# Master.net
KiCad netlist of a schematic drawn in EAGLE
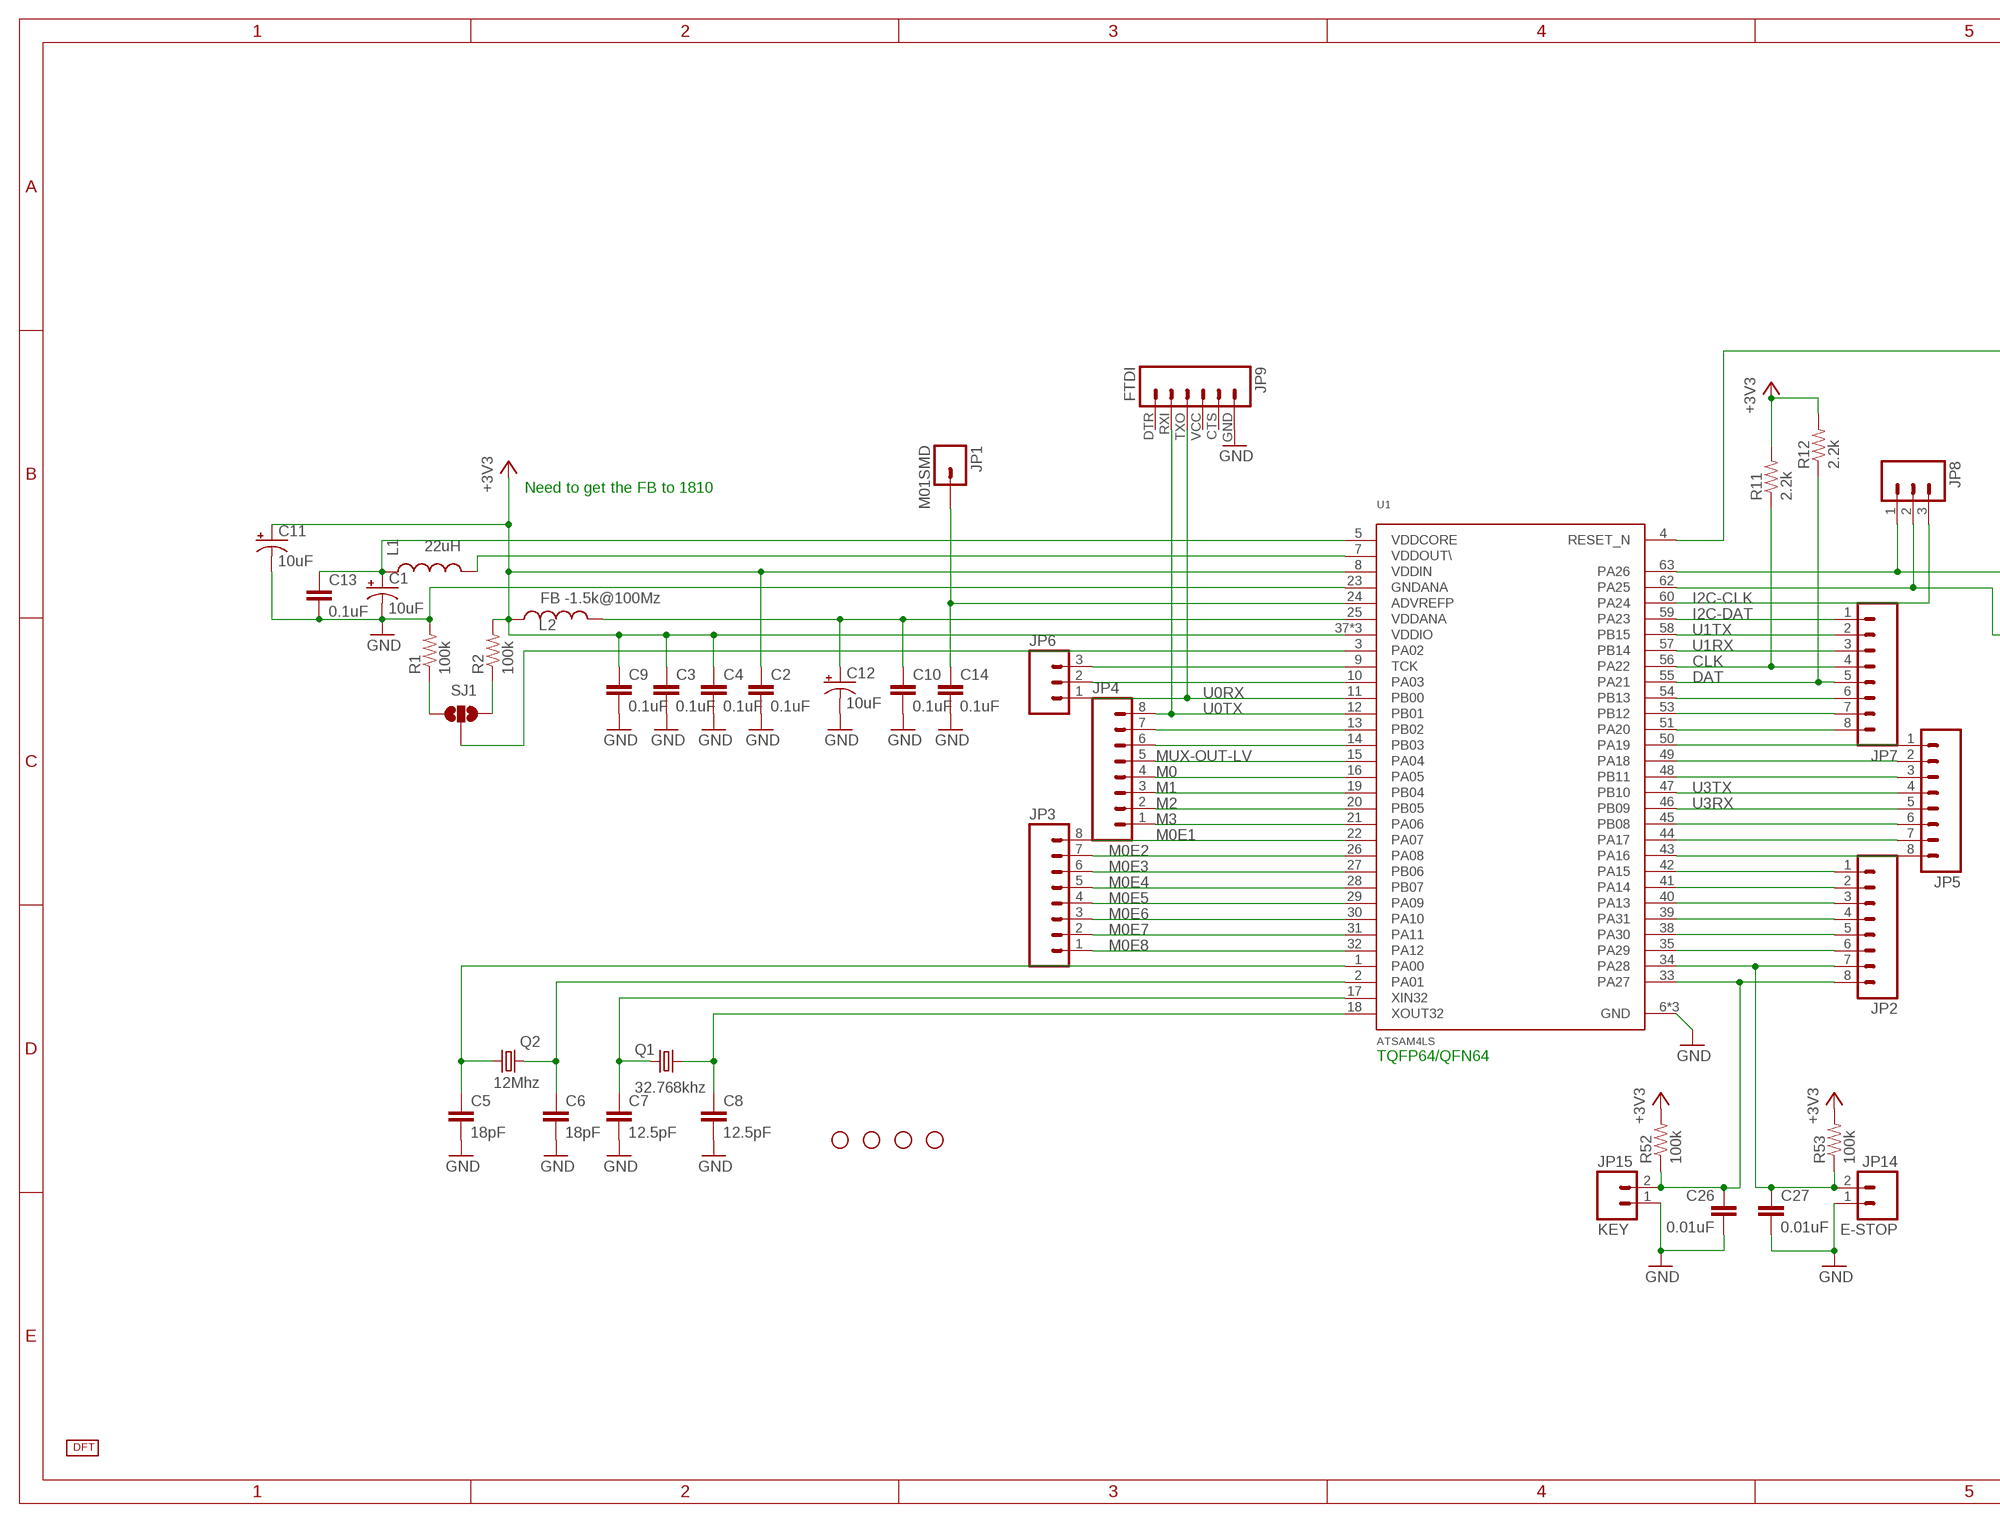
[diagram p0: schematic, sheet 1, part 1 of 2]
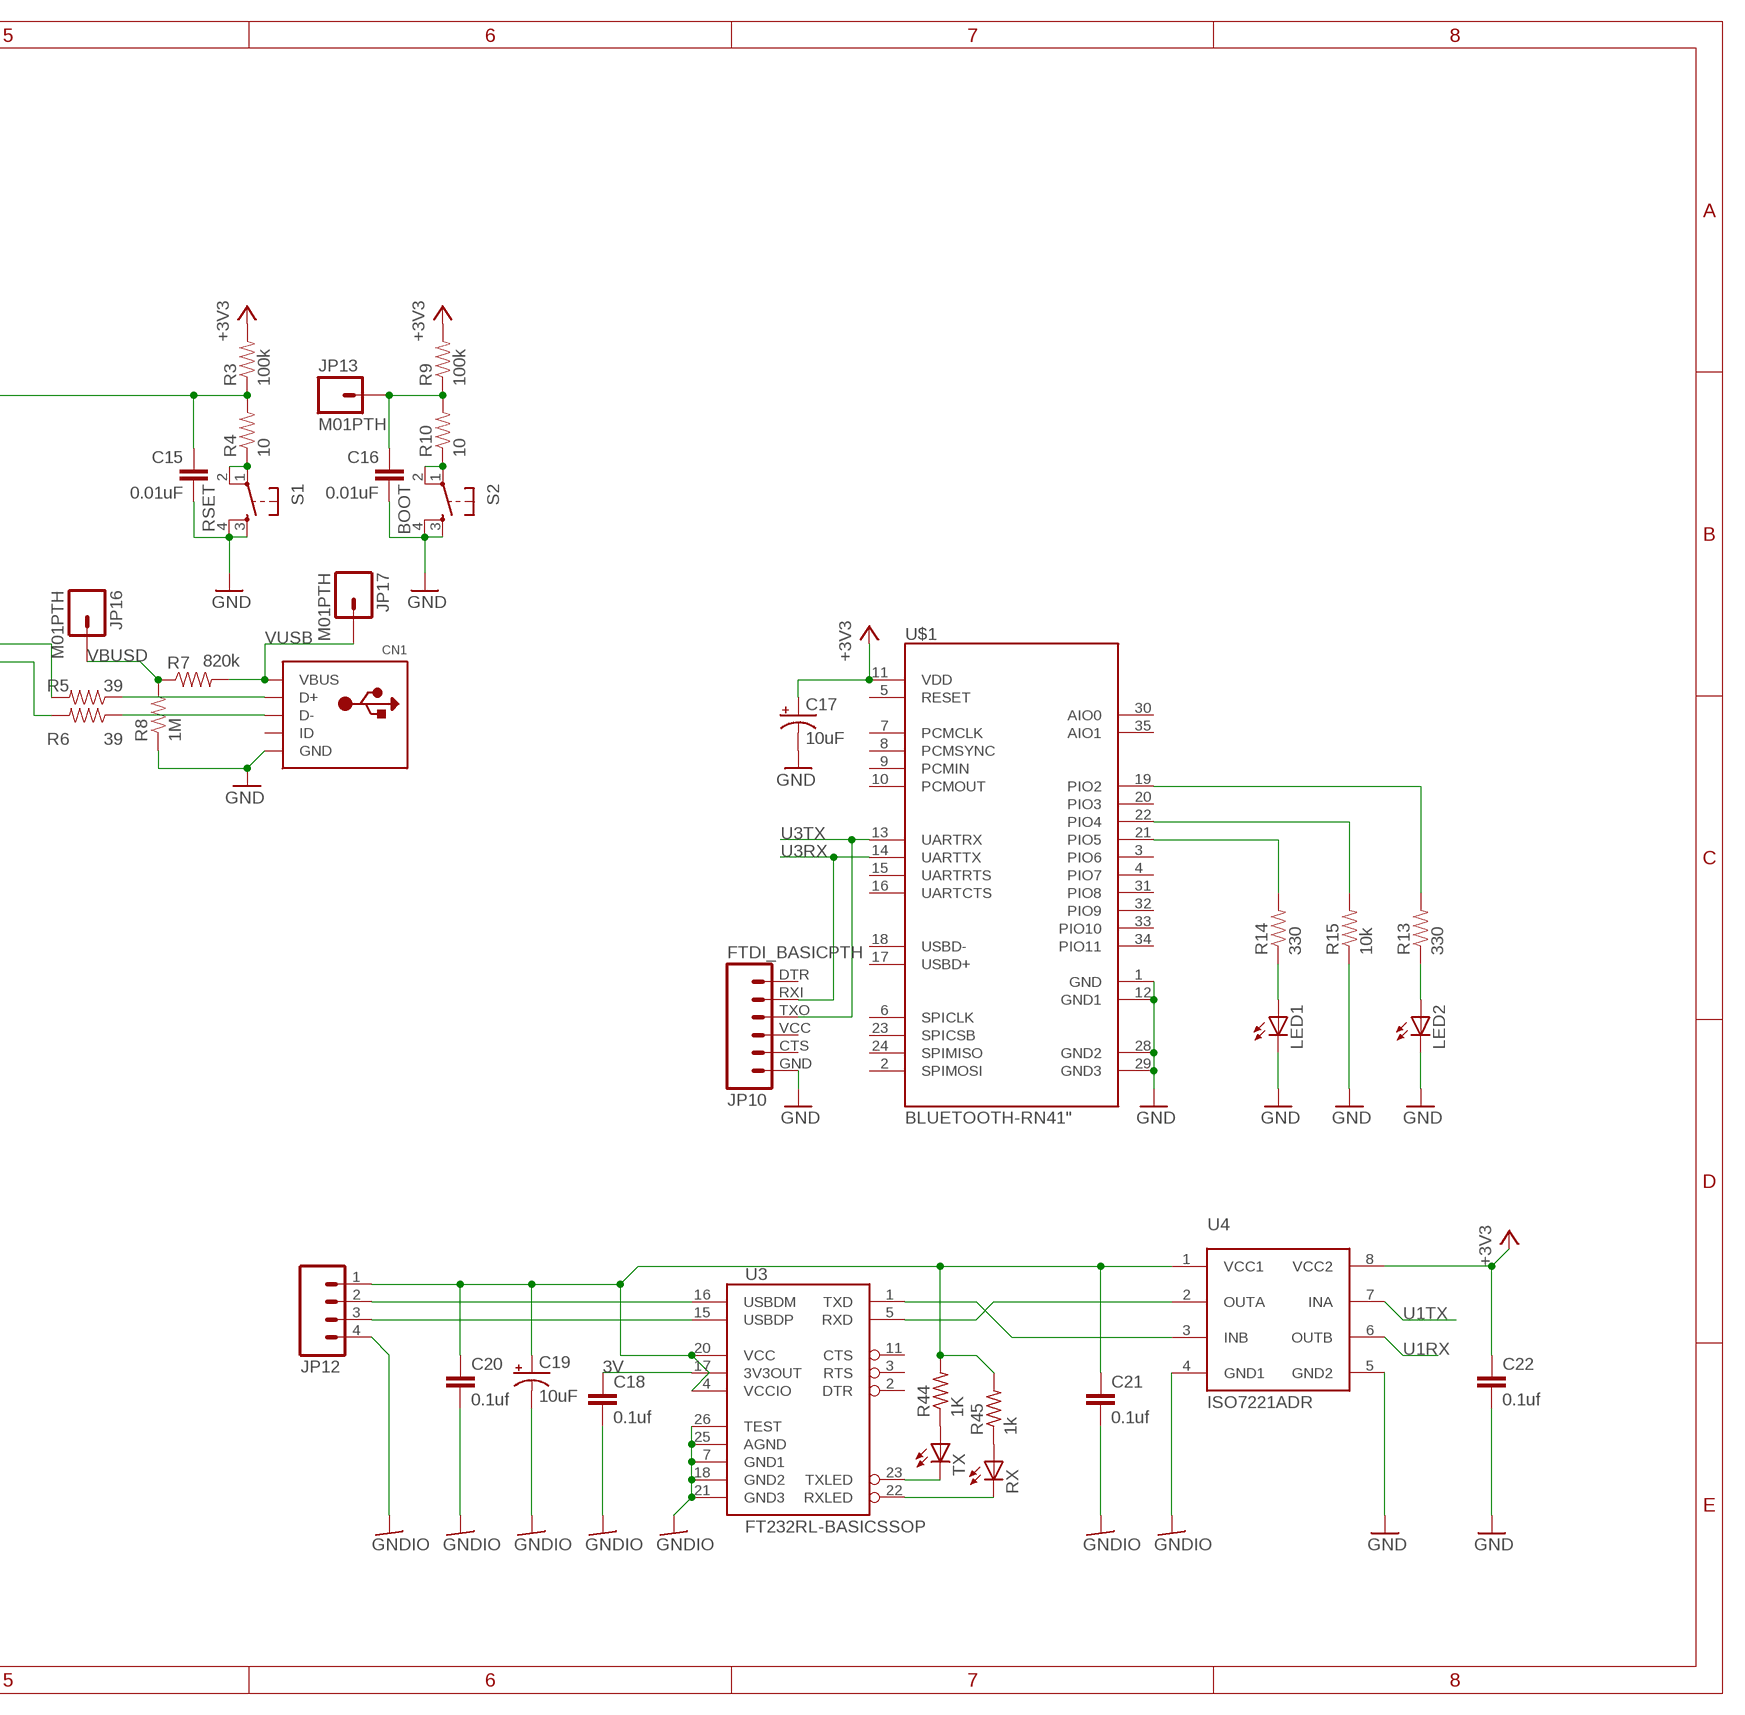
[diagram p1: schematic, sheet 1, part 2 of 2]
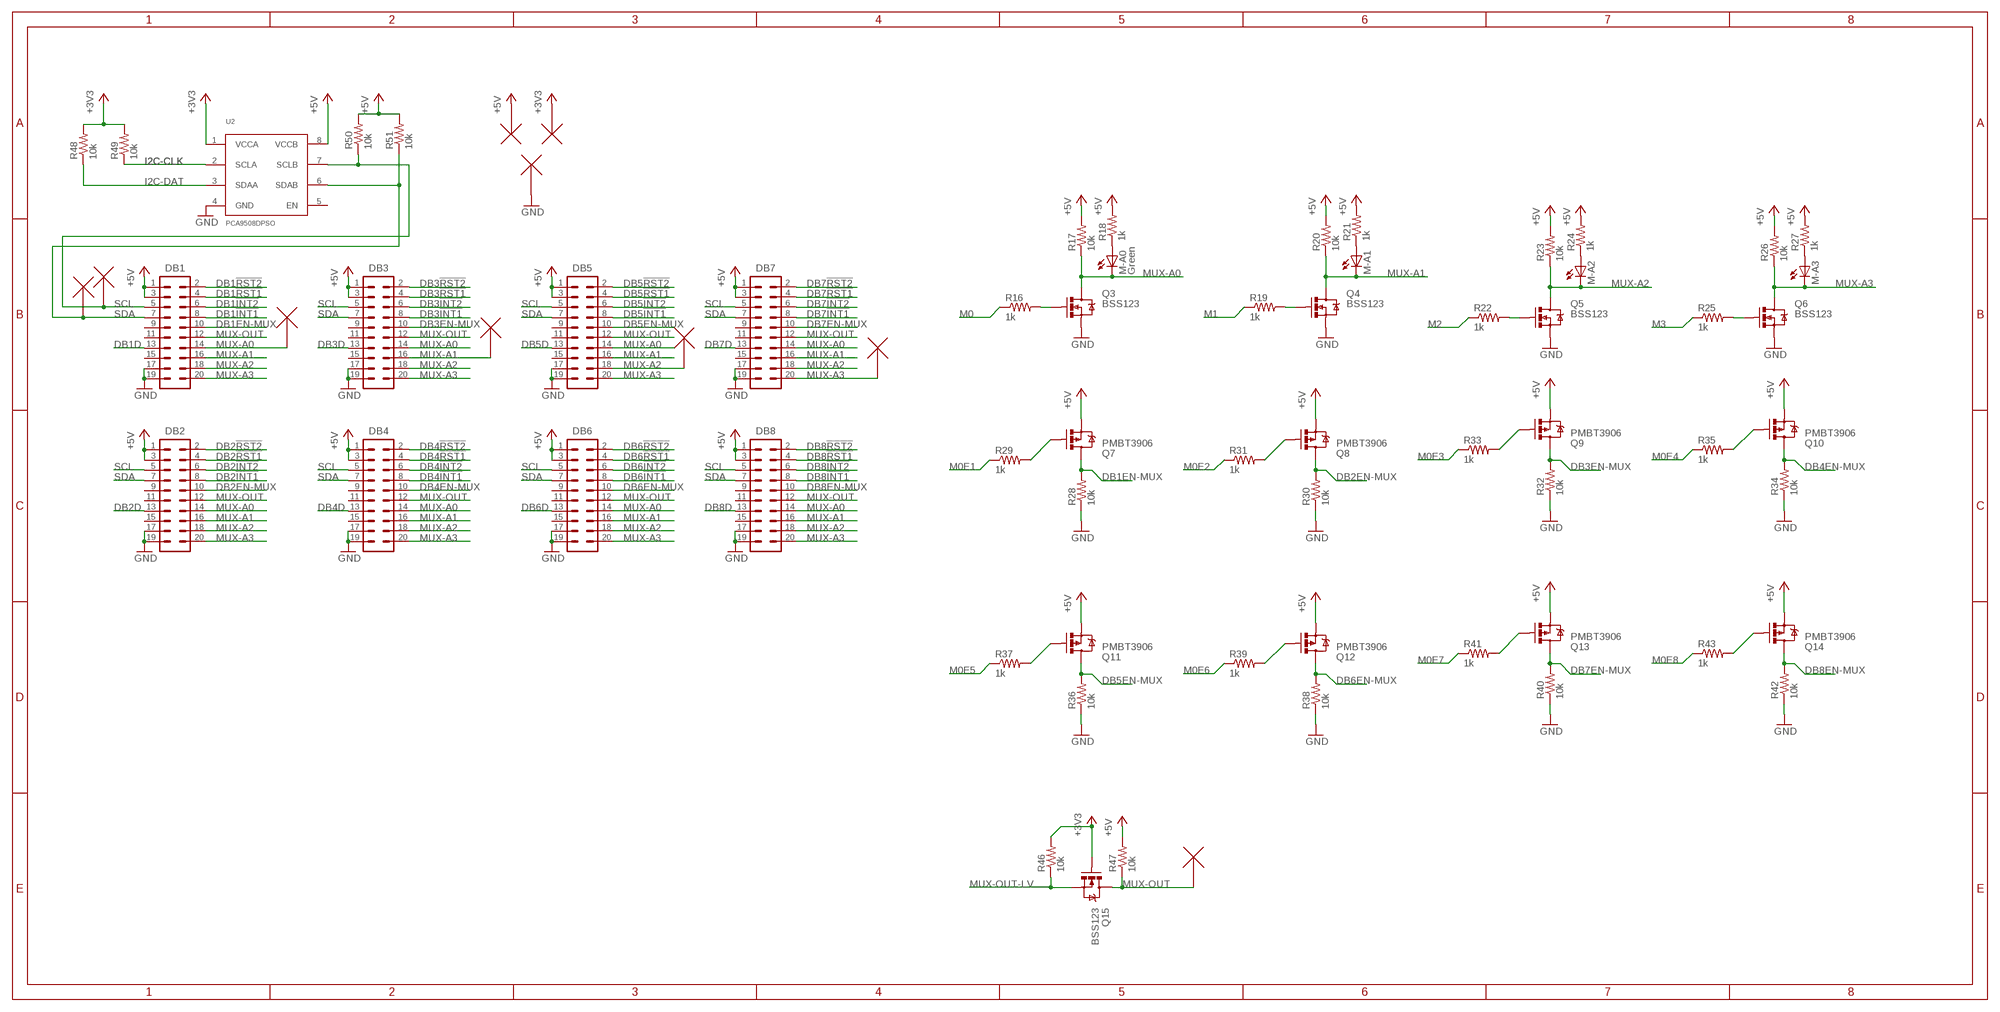
[diagram p2: schematic, sheet 2]
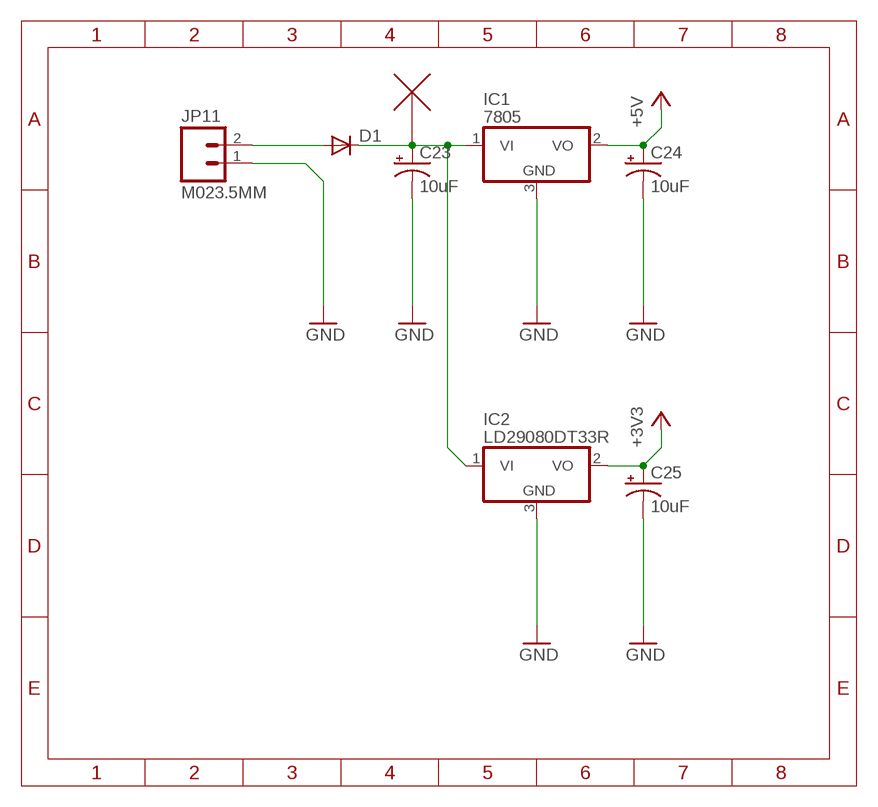
[diagram p3: schematic, sheet 3]

(export (version "E")
  (design (tool "Eeschema 10.0.6"))
  (components
    (comp (ref "C1")
      (value "10uF")
      (footprint "eagle-import:EIA3216")
      (libsource (lib "eagle-import") (part "SparkFun-Passives_CAP_POL1206"))
    )
    (comp (ref "C2")
      (value "0.1uF")
      (footprint "eagle-import:0805")
      (libsource (lib "eagle-import") (part "SparkFun-Passives_CAP0805"))
    )
    (comp (ref "C3")
      (value "0.1uF")
      (footprint "eagle-import:0805")
      (libsource (lib "eagle-import") (part "SparkFun-Passives_CAP0805"))
    )
    (comp (ref "C4")
      (value "0.1uF")
      (footprint "eagle-import:0805")
      (libsource (lib "eagle-import") (part "SparkFun-Passives_CAP0805"))
    )
    (comp (ref "C5")
      (value "18pF")
      (footprint "eagle-import:0805")
      (libsource (lib "eagle-import") (part "SparkFun-Passives_CAP0805"))
    )
    (comp (ref "C6")
      (value "18pF")
      (footprint "eagle-import:0805")
      (libsource (lib "eagle-import") (part "SparkFun-Passives_CAP0805"))
    )
    (comp (ref "C7")
      (value "12.5pF")
      (footprint "eagle-import:0805")
      (libsource (lib "eagle-import") (part "SparkFun-Passives_CAP0805"))
    )
    (comp (ref "C8")
      (value "12.5pF")
      (footprint "eagle-import:0805")
      (libsource (lib "eagle-import") (part "SparkFun-Passives_CAP0805"))
    )
    (comp (ref "C9")
      (value "0.1uF")
      (footprint "eagle-import:0805")
      (libsource (lib "eagle-import") (part "SparkFun-Passives_CAP0805"))
    )
    (comp (ref "C10")
      (value "0.1uF")
      (footprint "eagle-import:0805")
      (libsource (lib "eagle-import") (part "SparkFun-Passives_CAP0805"))
    )
    (comp (ref "C11")
      (value "10uF")
      (footprint "eagle-import:EIA3216")
      (libsource (lib "eagle-import") (part "10UF-16V-10%(TANT)"))
    )
    (comp (ref "C12")
      (value "10uF")
      (footprint "eagle-import:EIA3216")
      (libsource (lib "eagle-import") (part "SparkFun-Passives_CAP_POL1206"))
    )
    (comp (ref "C13")
      (value "0.1uF")
      (footprint "eagle-import:0805")
      (libsource (lib "eagle-import") (part "SparkFun-Passives_CAP0805"))
    )
    (comp (ref "C14")
      (value "0.1uF")
      (footprint "eagle-import:0805")
      (libsource (lib "eagle-import") (part "SparkFun-Passives_CAP0805"))
    )
    (comp (ref "C15")
      (value "0.01uF")
      (footprint "eagle-import:0805")
      (libsource (lib "eagle-import") (part "SparkFun-Passives_CAP0805"))
    )
    (comp (ref "C16")
      (value "0.01uF")
      (footprint "eagle-import:0805")
      (libsource (lib "eagle-import") (part "SparkFun-Passives_CAP0805"))
    )
    (comp (ref "C17")
      (value "10uF")
      (footprint "eagle-import:EIA3216")
      (libsource (lib "eagle-import") (part "SparkFun-Passives_CAP_POL1206"))
    )
    (comp (ref "C18")
      (value "0.1uf")
      (footprint "eagle-import:0805")
      (libsource (lib "eagle-import") (part "CAP0805"))
    )
    (comp (ref "C19")
      (value "10uF")
      (footprint "eagle-import:EIA3216")
      (libsource (lib "eagle-import") (part "CAP_POL1206"))
    )
    (comp (ref "C20")
      (value "0.1uf")
      (footprint "eagle-import:0805")
      (libsource (lib "eagle-import") (part "CAP0805"))
    )
    (comp (ref "C21")
      (value "0.1uf")
      (footprint "eagle-import:0805")
      (libsource (lib "eagle-import") (part "CAP0805"))
    )
    (comp (ref "C22")
      (value "0.1uf")
      (footprint "eagle-import:0805")
      (libsource (lib "eagle-import") (part "CAP0805"))
    )
    (comp (ref "C26")
      (value "0.01uF")
      (footprint "eagle-import:0805")
      (libsource (lib "eagle-import") (part "SparkFun-Passives_CAP0805"))
    )
    (comp (ref "C27")
      (value "0.01uF")
      (footprint "eagle-import:0805")
      (libsource (lib "eagle-import") (part "SparkFun-Passives_CAP0805"))
    )
    (comp (ref "CN1")
      (value "USBMOLEX")
      (footprint "eagle-import:USB-MINIB-THM-MOLEX")
      (libsource (lib "eagle-import") (part "USBMOLEX"))
    )
    (comp (ref "JP1")
      (value "M01SMD")
      (footprint "eagle-import:LUXEON-PAD")
      (libsource (lib "eagle-import") (part "M01SMD"))
    )
    (comp (ref "JP2")
      (value "M08LOCK")
      (footprint "eagle-import:1X08_LOCK")
      (libsource (lib "eagle-import") (part "M08LOCK"))
    )
    (comp (ref "JP3")
      (value "M08LOCK")
      (footprint "eagle-import:1X08_LOCK")
      (libsource (lib "eagle-import") (part "M08LOCK"))
    )
    (comp (ref "JP4")
      (value "M08LOCK")
      (footprint "eagle-import:1X08_LOCK")
      (libsource (lib "eagle-import") (part "M08LOCK"))
    )
    (comp (ref "JP5")
      (value "M08LOCK")
      (footprint "eagle-import:1X08_LOCK")
      (libsource (lib "eagle-import") (part "M08LOCK"))
    )
    (comp (ref "JP6")
      (value "M03LOCK")
      (footprint "eagle-import:1X03_LOCK")
      (libsource (lib "eagle-import") (part "M03LOCK"))
    )
    (comp (ref "JP7")
      (value "M08LOCK")
      (footprint "eagle-import:1X08_LOCK")
      (libsource (lib "eagle-import") (part "M08LOCK"))
    )
    (comp (ref "JP8")
      (value "M03LOCK")
      (footprint "eagle-import:1X03_LOCK")
      (libsource (lib "eagle-import") (part "M03LOCK"))
    )
    (comp (ref "JP9")
      (value "FTDI")
      (footprint "eagle-import:FTDI_BASIC")
      (libsource (lib "eagle-import") (part "FTDI_BASICPTH"))
    )
    (comp (ref "JP10")
      (value "FTDI_BASICPTH")
      (footprint "eagle-import:FTDI_BASIC")
      (libsource (lib "eagle-import") (part "FTDI_BASICPTH"))
    )
    (comp (ref "JP12")
      (value "M04POLAR_LOCK")
      (footprint "eagle-import:MOLEX-1X4_LOCK")
      (libsource (lib "eagle-import") (part "M04POLAR_LOCK"))
    )
    (comp (ref "JP13")
      (value "M01PTH")
      (footprint "eagle-import:1X01")
      (libsource (lib "eagle-import") (part "M01PTH"))
    )
    (comp (ref "JP14")
      (value "E-STOP")
      (footprint "eagle-import:1X02_LOCK")
      (libsource (lib "eagle-import") (part "M02LOCK"))
    )
    (comp (ref "JP15")
      (value "KEY")
      (footprint "eagle-import:1X02_LOCK")
      (libsource (lib "eagle-import") (part "M02LOCK"))
    )
    (comp (ref "JP16")
      (value "M01PTH")
      (footprint "eagle-import:1X01")
      (libsource (lib "eagle-import") (part "M01PTH"))
    )
    (comp (ref "JP17")
      (value "M01PTH")
      (footprint "eagle-import:1X01")
      (libsource (lib "eagle-import") (part "M01PTH"))
    )
    (comp (ref "L1")
      (value "22uH")
      (footprint "eagle-import:0805")
      (libsource (lib "eagle-import") (part "INDUCTOR0805"))
    )
    (comp (ref "L2")
      (value "FB -1.5k@100Mz")
      (footprint "eagle-import:0805")
      (libsource (lib "eagle-import") (part "INDUCTOR0805"))
    )
    (comp (ref "LED1")
      (value "LEDCHIP-LED0805")
      (footprint "eagle-import:CHIP-LED0805")
      (libsource (lib "eagle-import") (part "LEDCHIP-LED0805"))
    )
    (comp (ref "LED2")
      (value "LEDCHIP-LED0805")
      (footprint "eagle-import:CHIP-LED0805")
      (libsource (lib "eagle-import") (part "LEDCHIP-LED0805"))
    )
    (comp (ref "Q1")
      (value "32.768khz")
      (footprint "eagle-import:MM20SS")
      (libsource (lib "eagle-import") (part "CRYSTALMM20SS"))
    )
    (comp (ref "Q2")
      (value "12Mhz")
      (footprint "eagle-import:CTS406")
      (libsource (lib "eagle-import") (part "CRYSTALCTS406"))
    )
    (comp (ref "R1")
      (value "100k")
      (footprint "eagle-import:0805")
      (libsource (lib "eagle-import") (part "RESISTOR0805-RES"))
    )
    (comp (ref "R2")
      (value "100k")
      (footprint "eagle-import:0805")
      (libsource (lib "eagle-import") (part "RESISTOR0805-RES"))
    )
    (comp (ref "R3")
      (value "100k")
      (footprint "eagle-import:0805")
      (libsource (lib "eagle-import") (part "RESISTOR0805-RES"))
    )
    (comp (ref "R4")
      (value "10")
      (footprint "eagle-import:0805")
      (libsource (lib "eagle-import") (part "RESISTOR0805-RES"))
    )
    (comp (ref "R5")
      (value "39")
      (footprint "eagle-import:0805")
      (libsource (lib "eagle-import") (part "RESISTOR0805-RES"))
    )
    (comp (ref "R6")
      (value "39")
      (footprint "eagle-import:0805")
      (libsource (lib "eagle-import") (part "RESISTOR0805-RES"))
    )
    (comp (ref "R7")
      (value "820k")
      (footprint "eagle-import:0805")
      (libsource (lib "eagle-import") (part "RESISTOR0805-RES"))
    )
    (comp (ref "R8")
      (value "1M")
      (footprint "eagle-import:0805")
      (libsource (lib "eagle-import") (part "RESISTOR0805-RES"))
    )
    (comp (ref "R9")
      (value "100k")
      (footprint "eagle-import:0805")
      (libsource (lib "eagle-import") (part "RESISTOR0805-RES"))
    )
    (comp (ref "R10")
      (value "10")
      (footprint "eagle-import:0805")
      (libsource (lib "eagle-import") (part "RESISTOR0805-RES"))
    )
    (comp (ref "R11")
      (value "2.2k")
      (footprint "eagle-import:0805")
      (libsource (lib "eagle-import") (part "RESISTOR0805-RES"))
    )
    (comp (ref "R12")
      (value "2.2k")
      (footprint "eagle-import:0805")
      (libsource (lib "eagle-import") (part "RESISTOR0805-RES"))
    )
    (comp (ref "R13")
      (value "330")
      (footprint "eagle-import:0805")
      (libsource (lib "eagle-import") (part "RESISTOR0805-RES"))
    )
    (comp (ref "R14")
      (value "330")
      (footprint "eagle-import:0805")
      (libsource (lib "eagle-import") (part "RESISTOR0805-RES"))
    )
    (comp (ref "R15")
      (value "10k")
      (footprint "eagle-import:0805")
      (libsource (lib "eagle-import") (part "RESISTOR0805-RES"))
    )
    (comp (ref "R44")
      (value "1K")
      (footprint "eagle-import:R0805")
      (libsource (lib "eagle-import") (part "R-US_R0805"))
    )
    (comp (ref "R45")
      (value "1k")
      (footprint "eagle-import:R0805")
      (libsource (lib "eagle-import") (part "R-US_R0805"))
    )
    (comp (ref "R52")
      (value "100k")
      (footprint "eagle-import:0805")
      (libsource (lib "eagle-import") (part "RESISTOR0805-RES"))
    )
    (comp (ref "R53")
      (value "100k")
      (footprint "eagle-import:0805")
      (libsource (lib "eagle-import") (part "RESISTOR0805-RES"))
    )
    (comp (ref "RX")
      (value "LEDCHIPLED_0805")
      (footprint "eagle-import:CHIPLED_0805")
      (libsource (lib "eagle-import") (part "LEDCHIPLED_0805"))
    )
    (comp (ref "S1")
      (value "RSET")
      (footprint "eagle-import:TACTILE-PTH")
      (libsource (lib "eagle-import") (part "TAC_SWITCHPTH"))
    )
    (comp (ref "S2")
      (value "BOOT")
      (footprint "eagle-import:TACTILE-PTH")
      (libsource (lib "eagle-import") (part "TAC_SWITCHPTH"))
    )
    (comp (ref "SJ1")
      (value "SOLDERJUMPER_2WAYS")
      (footprint "eagle-import:SJ_3")
      (libsource (lib "eagle-import") (part "SOLDERJUMPER_2WAYS"))
    )
    (comp (ref "STANDOFF1")
      (value "STAND-OFF")
      (footprint "eagle-import:STAND-OFF")
      (libsource (lib "eagle-import") (part "STAND-OFF"))
    )
    (comp (ref "STANDOFF2")
      (value "STAND-OFF")
      (footprint "eagle-import:STAND-OFF")
      (libsource (lib "eagle-import") (part "STAND-OFF"))
    )
    (comp (ref "STANDOFF3")
      (value "STAND-OFF")
      (footprint "eagle-import:STAND-OFF")
      (libsource (lib "eagle-import") (part "STAND-OFF"))
    )
    (comp (ref "STANDOFF4")
      (value "STAND-OFF")
      (footprint "eagle-import:STAND-OFF")
      (libsource (lib "eagle-import") (part "STAND-OFF"))
    )
    (comp (ref "TX")
      (value "LEDCHIPLED_0805")
      (footprint "eagle-import:CHIPLED_0805")
      (libsource (lib "eagle-import") (part "LEDCHIPLED_0805"))
    )
    (comp (ref "U$1")
      (value "BLUETOOTH-RN41\"")
      (footprint "eagle-import:RN41")
      (libsource (lib "eagle-import") (part "BLUETOOTH-RN41{dblquote}"))
    )
    (comp (ref "U$12")
      (value "LOGO")
      (footprint "eagle-import:LOGO-S")
      (libsource (lib "eagle-import") (part "LOGO"))
    )
    (comp (ref "U1")
      (value "ATSAM4LS")
      (footprint "eagle-import:TQFP-64")
      (libsource (lib "eagle-import") (part "SAM4L"))
    )
    (comp (ref "U3")
      (value "FT232RL-BASICSSOP")
      (footprint "eagle-import:SSOP28DB")
      (libsource (lib "eagle-import") (part "FT232RL-BASICSSOP"))
    )
    (comp (ref "U4")
      (value "ISO7221ADR")
      (footprint "eagle-import:SOIC-8")
      (libsource (lib "eagle-import") (part "ISO7221ADR"))
    )
    (comp (ref "DB1")
      (value "M10X2SPECIAL")
      (footprint "eagle-import:2X10_LOCK_SPECIAL")
      (libsource (lib "eagle-import") (part "M10X2SPECIAL"))
    )
    (comp (ref "DB2")
      (value "M10X2SPECIAL")
      (footprint "eagle-import:2X10_LOCK_SPECIAL")
      (libsource (lib "eagle-import") (part "M10X2SPECIAL"))
    )
    (comp (ref "DB3")
      (value "M10X2SPECIAL")
      (footprint "eagle-import:2X10_LOCK_SPECIAL")
      (libsource (lib "eagle-import") (part "M10X2SPECIAL"))
    )
    (comp (ref "DB4")
      (value "M10X2SPECIAL")
      (footprint "eagle-import:2X10_LOCK_SPECIAL")
      (libsource (lib "eagle-import") (part "M10X2SPECIAL"))
    )
    (comp (ref "DB5")
      (value "M10X2SPECIAL")
      (footprint "eagle-import:2X10_LOCK_SPECIAL")
      (libsource (lib "eagle-import") (part "M10X2SPECIAL"))
    )
    (comp (ref "DB6")
      (value "M10X2SPECIAL")
      (footprint "eagle-import:2X10_LOCK_SPECIAL")
      (libsource (lib "eagle-import") (part "M10X2SPECIAL"))
    )
    (comp (ref "DB7")
      (value "M10X2SPECIAL")
      (footprint "eagle-import:2X10_LOCK_SPECIAL")
      (libsource (lib "eagle-import") (part "M10X2SPECIAL"))
    )
    (comp (ref "DB8")
      (value "M10X2SPECIAL")
      (footprint "eagle-import:2X10_LOCK_SPECIAL")
      (libsource (lib "eagle-import") (part "M10X2SPECIAL"))
    )
    (comp (ref "M-A0")
      (value "Green")
      (footprint "eagle-import:CHIP-LED0805")
      (libsource (lib "eagle-import") (part "LEDCHIP-LED0805"))
    )
    (comp (ref "M-A1")
      (value "LEDCHIP-LED0805")
      (footprint "eagle-import:CHIP-LED0805")
      (libsource (lib "eagle-import") (part "LEDCHIP-LED0805"))
    )
    (comp (ref "M-A2")
      (value "LEDCHIP-LED0805")
      (footprint "eagle-import:CHIP-LED0805")
      (libsource (lib "eagle-import") (part "LEDCHIP-LED0805"))
    )
    (comp (ref "M-A3")
      (value "LEDCHIP-LED0805")
      (footprint "eagle-import:CHIP-LED0805")
      (libsource (lib "eagle-import") (part "LEDCHIP-LED0805"))
    )
    (comp (ref "Q3")
      (value "BSS123")
      (footprint "eagle-import:SOT23")
      (libsource (lib "eagle-import") (part "MOSFET-NCHANNELBSS123LT1G"))
    )
    (comp (ref "Q4")
      (value "BSS123")
      (footprint "eagle-import:SOT23")
      (libsource (lib "eagle-import") (part "MOSFET-NCHANNELBSS123LT1G"))
    )
    (comp (ref "Q5")
      (value "BSS123")
      (footprint "eagle-import:SOT23")
      (libsource (lib "eagle-import") (part "MOSFET-NCHANNELBSS123LT1G"))
    )
    (comp (ref "Q6")
      (value "BSS123")
      (footprint "eagle-import:SOT23")
      (libsource (lib "eagle-import") (part "MOSFET-NCHANNELBSS123LT1G"))
    )
    (comp (ref "Q7")
      (value "PMBT3906")
      (footprint "eagle-import:SOT23-3")
      (libsource (lib "eagle-import") (part "MOSFET-PCHANNELSMD"))
    )
    (comp (ref "Q8")
      (value "PMBT3906")
      (footprint "eagle-import:SOT23-3")
      (libsource (lib "eagle-import") (part "MOSFET-PCHANNELSMD"))
    )
    (comp (ref "Q9")
      (value "PMBT3906")
      (footprint "eagle-import:SOT23-3")
      (libsource (lib "eagle-import") (part "MOSFET-PCHANNELSMD"))
    )
    (comp (ref "Q10")
      (value "PMBT3906")
      (footprint "eagle-import:SOT23-3")
      (libsource (lib "eagle-import") (part "MOSFET-PCHANNELSMD"))
    )
    (comp (ref "Q11")
      (value "PMBT3906")
      (footprint "eagle-import:SOT23-3")
      (libsource (lib "eagle-import") (part "MOSFET-PCHANNELSMD"))
    )
    (comp (ref "Q12")
      (value "PMBT3906")
      (footprint "eagle-import:SOT23-3")
      (libsource (lib "eagle-import") (part "MOSFET-PCHANNELSMD"))
    )
    (comp (ref "Q13")
      (value "PMBT3906")
      (footprint "eagle-import:SOT23-3")
      (libsource (lib "eagle-import") (part "MOSFET-PCHANNELSMD"))
    )
    (comp (ref "Q14")
      (value "PMBT3906")
      (footprint "eagle-import:SOT23-3")
      (libsource (lib "eagle-import") (part "MOSFET-PCHANNELSMD"))
    )
    (comp (ref "Q15")
      (value "BSS123")
      (footprint "eagle-import:SOT23")
      (libsource (lib "eagle-import") (part "MOSFET-NCHANNELBSS123LT1G"))
    )
    (comp (ref "R16")
      (value "1k")
      (footprint "eagle-import:0805")
      (libsource (lib "eagle-import") (part "RESISTOR0805-RES"))
    )
    (comp (ref "R17")
      (value "10k")
      (footprint "eagle-import:0805")
      (libsource (lib "eagle-import") (part "RESISTOR0805-RES"))
    )
    (comp (ref "R18")
      (value "1k")
      (footprint "eagle-import:0805")
      (libsource (lib "eagle-import") (part "RESISTOR0805-RES"))
    )
    (comp (ref "R19")
      (value "1k")
      (footprint "eagle-import:0805")
      (libsource (lib "eagle-import") (part "RESISTOR0805-RES"))
    )
    (comp (ref "R20")
      (value "10k")
      (footprint "eagle-import:0805")
      (libsource (lib "eagle-import") (part "RESISTOR0805-RES"))
    )
    (comp (ref "R21")
      (value "1k")
      (footprint "eagle-import:0805")
      (libsource (lib "eagle-import") (part "RESISTOR0805-RES"))
    )
    (comp (ref "R22")
      (value "1k")
      (footprint "eagle-import:0805")
      (libsource (lib "eagle-import") (part "RESISTOR0805-RES"))
    )
    (comp (ref "R23")
      (value "10k")
      (footprint "eagle-import:0805")
      (libsource (lib "eagle-import") (part "RESISTOR0805-RES"))
    )
    (comp (ref "R24")
      (value "1k")
      (footprint "eagle-import:0805")
      (libsource (lib "eagle-import") (part "RESISTOR0805-RES"))
    )
    (comp (ref "R25")
      (value "1k")
      (footprint "eagle-import:0805")
      (libsource (lib "eagle-import") (part "RESISTOR0805-RES"))
    )
    (comp (ref "R26")
      (value "10k")
      (footprint "eagle-import:0805")
      (libsource (lib "eagle-import") (part "RESISTOR0805-RES"))
    )
    (comp (ref "R27")
      (value "1k")
      (footprint "eagle-import:0805")
      (libsource (lib "eagle-import") (part "RESISTOR0805-RES"))
    )
    (comp (ref "R28")
      (value "10k")
      (footprint "eagle-import:0805")
      (libsource (lib "eagle-import") (part "RESISTOR0805-RES"))
    )
    (comp (ref "R29")
      (value "1k")
      (footprint "eagle-import:0805")
      (libsource (lib "eagle-import") (part "RESISTOR0805-RES"))
    )
    (comp (ref "R30")
      (value "10k")
      (footprint "eagle-import:0805")
      (libsource (lib "eagle-import") (part "RESISTOR0805-RES"))
    )
    (comp (ref "R31")
      (value "1k")
      (footprint "eagle-import:0805")
      (libsource (lib "eagle-import") (part "RESISTOR0805-RES"))
    )
    (comp (ref "R32")
      (value "10k")
      (footprint "eagle-import:0805")
      (libsource (lib "eagle-import") (part "RESISTOR0805-RES"))
    )
    (comp (ref "R33")
      (value "1k")
      (footprint "eagle-import:0805")
      (libsource (lib "eagle-import") (part "RESISTOR0805-RES"))
    )
    (comp (ref "R34")
      (value "10k")
      (footprint "eagle-import:0805")
      (libsource (lib "eagle-import") (part "RESISTOR0805-RES"))
    )
    (comp (ref "R35")
      (value "1k")
      (footprint "eagle-import:0805")
      (libsource (lib "eagle-import") (part "RESISTOR0805-RES"))
    )
    (comp (ref "R36")
      (value "10k")
      (footprint "eagle-import:0805")
      (libsource (lib "eagle-import") (part "RESISTOR0805-RES"))
    )
    (comp (ref "R37")
      (value "1k")
      (footprint "eagle-import:0805")
      (libsource (lib "eagle-import") (part "RESISTOR0805-RES"))
    )
    (comp (ref "R38")
      (value "10k")
      (footprint "eagle-import:0805")
      (libsource (lib "eagle-import") (part "RESISTOR0805-RES"))
    )
    (comp (ref "R39")
      (value "1k")
      (footprint "eagle-import:0805")
      (libsource (lib "eagle-import") (part "RESISTOR0805-RES"))
    )
    (comp (ref "R40")
      (value "10k")
      (footprint "eagle-import:0805")
      (libsource (lib "eagle-import") (part "RESISTOR0805-RES"))
    )
    (comp (ref "R41")
      (value "1k")
      (footprint "eagle-import:0805")
      (libsource (lib "eagle-import") (part "RESISTOR0805-RES"))
    )
    (comp (ref "R42")
      (value "10k")
      (footprint "eagle-import:0805")
      (libsource (lib "eagle-import") (part "RESISTOR0805-RES"))
    )
    (comp (ref "R43")
      (value "1k")
      (footprint "eagle-import:0805")
      (libsource (lib "eagle-import") (part "RESISTOR0805-RES"))
    )
    (comp (ref "R46")
      (value "10k")
      (footprint "eagle-import:0805")
      (libsource (lib "eagle-import") (part "RESISTOR0805-RES"))
    )
    (comp (ref "R47")
      (value "10k")
      (footprint "eagle-import:0805")
      (libsource (lib "eagle-import") (part "RESISTOR0805-RES"))
    )
    (comp (ref "R48")
      (value "10k")
      (footprint "eagle-import:0805")
      (libsource (lib "eagle-import") (part "RESISTOR0805-RES"))
    )
    (comp (ref "R49")
      (value "10k")
      (footprint "eagle-import:0805")
      (libsource (lib "eagle-import") (part "RESISTOR0805-RES"))
    )
    (comp (ref "R50")
      (value "10k")
      (footprint "eagle-import:0805")
      (libsource (lib "eagle-import") (part "RESISTOR0805-RES"))
    )
    (comp (ref "R51")
      (value "10k")
      (footprint "eagle-import:0805")
      (libsource (lib "eagle-import") (part "RESISTOR0805-RES"))
    )
    (comp (ref "U$2")
      (value "TESTPOINT")
      (footprint "eagle-import:R0603")
      (libsource (lib "eagle-import") (part "TESTPOINT"))
    )
    (comp (ref "U$3")
      (value "TESTPOINT")
      (footprint "eagle-import:R0603")
      (libsource (lib "eagle-import") (part "TESTPOINT"))
    )
    (comp (ref "U$4")
      (value "TESTPOINT")
      (footprint "eagle-import:R0603")
      (libsource (lib "eagle-import") (part "TESTPOINT"))
    )
    (comp (ref "U$5")
      (value "TESTPOINT")
      (footprint "eagle-import:R0603")
      (libsource (lib "eagle-import") (part "TESTPOINT"))
    )
    (comp (ref "U$6")
      (value "TESTPOINT")
      (footprint "eagle-import:R0603")
      (libsource (lib "eagle-import") (part "TESTPOINT"))
    )
    (comp (ref "U$7")
      (value "TESTPOINT")
      (footprint "eagle-import:R0603")
      (libsource (lib "eagle-import") (part "TESTPOINT"))
    )
    (comp (ref "U$8")
      (value "TESTPOINT")
      (footprint "eagle-import:R0603")
      (libsource (lib "eagle-import") (part "TESTPOINT"))
    )
    (comp (ref "U$9")
      (value "TESTPOINT")
      (footprint "eagle-import:R0603")
      (libsource (lib "eagle-import") (part "TESTPOINT"))
    )
    (comp (ref "U$10")
      (value "TESTPOINT")
      (footprint "eagle-import:R0603")
      (libsource (lib "eagle-import") (part "TESTPOINT"))
    )
    (comp (ref "U$13")
      (value "TESTPOINT")
      (footprint "eagle-import:R0603")
      (libsource (lib "eagle-import") (part "TESTPOINT"))
    )
    (comp (ref "U2")
      (value "PCA9508DPSO")
      (footprint "eagle-import:SO-8")
      (libsource (lib "eagle-import") (part "PCA9508DPSO"))
    )
    (comp (ref "C23")
      (value "10uF")
      (footprint "eagle-import:EIA6032")
      (libsource (lib "eagle-import") (part "SparkFun-Passives_CAP_POL6032"))
    )
    (comp (ref "C24")
      (value "10uF")
      (footprint "eagle-import:EIA3216")
      (libsource (lib "eagle-import") (part "10UF-TANT"))
    )
    (comp (ref "C25")
      (value "10uF")
      (footprint "eagle-import:EIA3216")
      (libsource (lib "eagle-import") (part "10UF-TANT"))
    )
    (comp (ref "D1")
      (value "DIODESMA")
      (footprint "eagle-import:SMA-DIODE")
      (libsource (lib "eagle-import") (part "DIODESMA"))
    )
    (comp (ref "IC1")
      (value "7805")
      (footprint "eagle-import:TO252")
      (libsource (lib "eagle-import") (part "78DT06"))
    )
    (comp (ref "IC2")
      (value "LD29080DT33R")
      (footprint "eagle-import:TO252")
      (libsource (lib "eagle-import") (part "78DT06"))
    )
    (comp (ref "JP11")
      (value "M023.5MM")
      (footprint "eagle-import:SCREWTERMINAL-3.5MM-2")
      (libsource (lib "eagle-import") (part "M023.5MM"))
    )
    (comp (ref "U$11")
      (value "TESTPOINT")
      (footprint "eagle-import:R0603")
      (libsource (lib "eagle-import") (part "TESTPOINT"))
    )
  )
  (nets
    (net (code "1") (name "+3V3") (class "Default")
      (node (ref "C11") (pin "A") (pinfunction "+_A") (pintype "passive"))
      (node (ref "C17") (pin "A") (pinfunction "+_A") (pintype "passive"))
      (node (ref "C2") (pin "1") (pinfunction "1_1") (pintype "passive"))
      (node (ref "C22") (pin "1") (pinfunction "1_1") (pintype "passive"))
      (node (ref "C25") (pin "A") (pinfunction "+_A") (pintype "passive"))
      (node (ref "C3") (pin "1") (pinfunction "1_1") (pintype "passive"))
      (node (ref "C4") (pin "1") (pinfunction "1_1") (pintype "passive"))
      (node (ref "C9") (pin "1") (pinfunction "1_1") (pintype "passive"))
      (node (ref "IC2") (pin "2") (pinfunction "VO_2") (pintype "passive"))
      (node (ref "L2") (pin "1") (pinfunction "1_1") (pintype "passive"))
      (node (ref "Q15") (pin "1") (pinfunction "G_1") (pintype "passive"))
      (node (ref "R11") (pin "2") (pinfunction "2_2") (pintype "passive"))
      (node (ref "R12") (pin "2") (pinfunction "2_2") (pintype "passive"))
      (node (ref "R2") (pin "2") (pinfunction "2_2") (pintype "passive"))
      (node (ref "R3") (pin "2") (pinfunction "2_2") (pintype "passive"))
      (node (ref "R46") (pin "2") (pinfunction "2_2") (pintype "passive"))
      (node (ref "R48") (pin "2") (pinfunction "2_2") (pintype "passive"))
      (node (ref "R49") (pin "2") (pinfunction "2_2") (pintype "passive"))
      (node (ref "R52") (pin "2") (pinfunction "2_2") (pintype "passive"))
      (node (ref "R53") (pin "2") (pinfunction "2_2") (pintype "passive"))
      (node (ref "R9") (pin "2") (pinfunction "2_2") (pintype "passive"))
      (node (ref "U$1") (pin "11") (pinfunction "VDD_11") (pintype "bidirectional"))
      (node (ref "U$9") (pin "1") (pinfunction "P$1_1") (pintype "bidirectional"))
      (node (ref "U$9") (pin "2") (pinfunction "P$1_2") (pintype "bidirectional"))
      (node (ref "U1") (pin "37") (pinfunction "VDDIO_37") (pintype "bidirectional"))
      (node (ref "U1") (pin "52") (pinfunction "VDDIO_52") (pintype "bidirectional"))
      (node (ref "U1") (pin "61") (pinfunction "VDDIO_61") (pintype "bidirectional"))
      (node (ref "U1") (pin "8") (pinfunction "VDDIN_8") (pintype "bidirectional"))
      (node (ref "U2") (pin "1") (pinfunction "VCCA_1") (pintype "bidirectional"))
      (node (ref "U4") (pin "8") (pinfunction "VCC2_8") (pintype "bidirectional"))
    )
    (net (code "2") (name "+5V") (class "Default")
      (node (ref "C24") (pin "A") (pinfunction "+_A") (pintype "passive"))
      (node (ref "DB1") (pin "1") (pinfunction "1_1") (pintype "passive"))
      (node (ref "DB1") (pin "3") (pinfunction "3_3") (pintype "passive"))
      (node (ref "DB2") (pin "1") (pinfunction "1_1") (pintype "passive"))
      (node (ref "DB2") (pin "3") (pinfunction "3_3") (pintype "passive"))
      (node (ref "DB3") (pin "1") (pinfunction "1_1") (pintype "passive"))
      (node (ref "DB3") (pin "3") (pinfunction "3_3") (pintype "passive"))
      (node (ref "DB4") (pin "1") (pinfunction "1_1") (pintype "passive"))
      (node (ref "DB4") (pin "3") (pinfunction "3_3") (pintype "passive"))
      (node (ref "DB5") (pin "1") (pinfunction "1_1") (pintype "passive"))
      (node (ref "DB5") (pin "3") (pinfunction "3_3") (pintype "passive"))
      (node (ref "DB6") (pin "1") (pinfunction "1_1") (pintype "passive"))
      (node (ref "DB6") (pin "3") (pinfunction "3_3") (pintype "passive"))
      (node (ref "DB7") (pin "1") (pinfunction "1_1") (pintype "passive"))
      (node (ref "DB7") (pin "3") (pinfunction "3_3") (pintype "passive"))
      (node (ref "DB8") (pin "1") (pinfunction "1_1") (pintype "passive"))
      (node (ref "DB8") (pin "3") (pinfunction "3_3") (pintype "passive"))
      (node (ref "IC1") (pin "2") (pinfunction "VO_2") (pintype "passive"))
      (node (ref "Q10") (pin "2") (pinfunction "S_2") (pintype "passive"))
      (node (ref "Q11") (pin "2") (pinfunction "S_2") (pintype "passive"))
      (node (ref "Q12") (pin "2") (pinfunction "S_2") (pintype "passive"))
      (node (ref "Q13") (pin "2") (pinfunction "S_2") (pintype "passive"))
      (node (ref "Q14") (pin "2") (pinfunction "S_2") (pintype "passive"))
      (node (ref "Q7") (pin "2") (pinfunction "S_2") (pintype "passive"))
      (node (ref "Q8") (pin "2") (pinfunction "S_2") (pintype "passive"))
      (node (ref "Q9") (pin "2") (pinfunction "S_2") (pintype "passive"))
      (node (ref "R17") (pin "2") (pinfunction "2_2") (pintype "passive"))
      (node (ref "R18") (pin "2") (pinfunction "2_2") (pintype "passive"))
      (node (ref "R20") (pin "2") (pinfunction "2_2") (pintype "passive"))
      (node (ref "R21") (pin "2") (pinfunction "2_2") (pintype "passive"))
      (node (ref "R23") (pin "2") (pinfunction "2_2") (pintype "passive"))
      (node (ref "R24") (pin "2") (pinfunction "2_2") (pintype "passive"))
      (node (ref "R26") (pin "2") (pinfunction "2_2") (pintype "passive"))
      (node (ref "R27") (pin "2") (pinfunction "2_2") (pintype "passive"))
      (node (ref "R47") (pin "2") (pinfunction "2_2") (pintype "passive"))
      (node (ref "R50") (pin "2") (pinfunction "2_2") (pintype "passive"))
      (node (ref "R51") (pin "2") (pinfunction "2_2") (pintype "passive"))
      (node (ref "U$8") (pin "1") (pinfunction "P$1_1") (pintype "bidirectional"))
      (node (ref "U$8") (pin "2") (pinfunction "P$1_2") (pintype "bidirectional"))
      (node (ref "U2") (pin "8") (pinfunction "VCCB_8") (pintype "bidirectional"))
    )
    (net (code "3") (name "3V") (class "Default")
      (node (ref "C18") (pin "1") (pinfunction "1_1") (pintype "passive"))
      (node (ref "U3") (pin "17") (pinfunction "3V3OUT_17") (pintype "output"))
    )
    (net (code "4") (name "CLK") (class "Default")
      (node (ref "JP7") (pin "4") (pinfunction "4_4") (pintype "passive"))
      (node (ref "R11") (pin "1") (pinfunction "1_1") (pintype "passive"))
      (node (ref "U1") (pin "56") (pinfunction "PA22_56") (pintype "bidirectional"))
    )
    (net (code "5") (name "DAT") (class "Default")
      (node (ref "JP7") (pin "5") (pinfunction "5_5") (pintype "passive"))
      (node (ref "R12") (pin "1") (pinfunction "1_1") (pintype "passive"))
      (node (ref "U1") (pin "55") (pinfunction "PA21_55") (pintype "bidirectional"))
    )
    (net (code "6") (name "DB1D") (class "Default")
      (node (ref "DB1") (pin "13") (pinfunction "13_13") (pintype "passive"))
    )
    (net (code "7") (name "DB1EN-MUX") (class "Default")
      (node (ref "DB1") (pin "10") (pinfunction "10_10") (pintype "passive"))
      (node (ref "Q7") (pin "3") (pinfunction "D_3") (pintype "passive"))
      (node (ref "R28") (pin "2") (pinfunction "2_2") (pintype "passive"))
    )
    (net (code "8") (name "DB1~{INT1}") (class "Default")
      (node (ref "DB1") (pin "8") (pinfunction "8_8") (pintype "passive"))
    )
    (net (code "9") (name "DB1~{INT2}") (class "Default")
      (node (ref "DB1") (pin "6") (pinfunction "6_6") (pintype "passive"))
    )
    (net (code "10") (name "DB1~{RST1}") (class "Default")
      (node (ref "DB1") (pin "4") (pinfunction "4_4") (pintype "passive"))
    )
    (net (code "11") (name "DB1~{RST2}") (class "Default")
      (node (ref "DB1") (pin "2") (pinfunction "2_2") (pintype "passive"))
    )
    (net (code "12") (name "DB2D") (class "Default")
      (node (ref "DB2") (pin "13") (pinfunction "13_13") (pintype "passive"))
    )
    (net (code "13") (name "DB2EN-MUX") (class "Default")
      (node (ref "DB2") (pin "10") (pinfunction "10_10") (pintype "passive"))
      (node (ref "Q8") (pin "3") (pinfunction "D_3") (pintype "passive"))
      (node (ref "R30") (pin "2") (pinfunction "2_2") (pintype "passive"))
    )
    (net (code "14") (name "DB2~{INT1}") (class "Default")
      (node (ref "DB2") (pin "8") (pinfunction "8_8") (pintype "passive"))
    )
    (net (code "15") (name "DB2~{INT2}") (class "Default")
      (node (ref "DB2") (pin "6") (pinfunction "6_6") (pintype "passive"))
    )
    (net (code "16") (name "DB2~{RST1}") (class "Default")
      (node (ref "DB2") (pin "4") (pinfunction "4_4") (pintype "passive"))
    )
    (net (code "17") (name "DB2~{RST2}") (class "Default")
      (node (ref "DB2") (pin "2") (pinfunction "2_2") (pintype "passive"))
    )
    (net (code "18") (name "DB3D") (class "Default")
      (node (ref "DB3") (pin "13") (pinfunction "13_13") (pintype "passive"))
    )
    (net (code "19") (name "DB3EN-MUX") (class "Default")
      (node (ref "DB3") (pin "10") (pinfunction "10_10") (pintype "passive"))
      (node (ref "Q9") (pin "3") (pinfunction "D_3") (pintype "passive"))
      (node (ref "R32") (pin "2") (pinfunction "2_2") (pintype "passive"))
    )
    (net (code "20") (name "DB3~{INT1}") (class "Default")
      (node (ref "DB3") (pin "8") (pinfunction "8_8") (pintype "passive"))
    )
    (net (code "21") (name "DB3~{INT2}") (class "Default")
      (node (ref "DB3") (pin "6") (pinfunction "6_6") (pintype "passive"))
    )
    (net (code "22") (name "DB3~{RST1}") (class "Default")
      (node (ref "DB3") (pin "4") (pinfunction "4_4") (pintype "passive"))
    )
    (net (code "23") (name "DB3~{RST2}") (class "Default")
      (node (ref "DB3") (pin "2") (pinfunction "2_2") (pintype "passive"))
    )
    (net (code "24") (name "DB4D") (class "Default")
      (node (ref "DB4") (pin "13") (pinfunction "13_13") (pintype "passive"))
    )
    (net (code "25") (name "DB4EN-MUX") (class "Default")
      (node (ref "DB4") (pin "10") (pinfunction "10_10") (pintype "passive"))
      (node (ref "Q10") (pin "3") (pinfunction "D_3") (pintype "passive"))
      (node (ref "R34") (pin "2") (pinfunction "2_2") (pintype "passive"))
    )
    (net (code "26") (name "DB4~{INT1}") (class "Default")
      (node (ref "DB4") (pin "8") (pinfunction "8_8") (pintype "passive"))
    )
    (net (code "27") (name "DB4~{INT2}") (class "Default")
      (node (ref "DB4") (pin "6") (pinfunction "6_6") (pintype "passive"))
    )
    (net (code "28") (name "DB4~{RST1}") (class "Default")
      (node (ref "DB4") (pin "4") (pinfunction "4_4") (pintype "passive"))
    )
    (net (code "29") (name "DB4~{RST2}") (class "Default")
      (node (ref "DB4") (pin "2") (pinfunction "2_2") (pintype "passive"))
    )
    (net (code "30") (name "DB5D") (class "Default")
      (node (ref "DB5") (pin "13") (pinfunction "13_13") (pintype "passive"))
    )
    (net (code "31") (name "DB5EN-MUX") (class "Default")
      (node (ref "DB5") (pin "10") (pinfunction "10_10") (pintype "passive"))
      (node (ref "Q11") (pin "3") (pinfunction "D_3") (pintype "passive"))
      (node (ref "R36") (pin "2") (pinfunction "2_2") (pintype "passive"))
    )
    (net (code "32") (name "DB5~{INT1}") (class "Default")
      (node (ref "DB5") (pin "8") (pinfunction "8_8") (pintype "passive"))
    )
    (net (code "33") (name "DB5~{INT2}") (class "Default")
      (node (ref "DB5") (pin "6") (pinfunction "6_6") (pintype "passive"))
    )
    (net (code "34") (name "DB5~{RST1}") (class "Default")
      (node (ref "DB5") (pin "4") (pinfunction "4_4") (pintype "passive"))
    )
    (net (code "35") (name "DB5~{RST2}") (class "Default")
      (node (ref "DB5") (pin "2") (pinfunction "2_2") (pintype "passive"))
    )
    (net (code "36") (name "DB6D") (class "Default")
      (node (ref "DB6") (pin "13") (pinfunction "13_13") (pintype "passive"))
    )
    (net (code "37") (name "DB6EN-MUX") (class "Default")
      (node (ref "DB6") (pin "10") (pinfunction "10_10") (pintype "passive"))
      (node (ref "Q12") (pin "3") (pinfunction "D_3") (pintype "passive"))
      (node (ref "R38") (pin "2") (pinfunction "2_2") (pintype "passive"))
    )
    (net (code "38") (name "DB6~{INT1}") (class "Default")
      (node (ref "DB6") (pin "8") (pinfunction "8_8") (pintype "passive"))
    )
    (net (code "39") (name "DB6~{INT2}") (class "Default")
      (node (ref "DB6") (pin "6") (pinfunction "6_6") (pintype "passive"))
    )
    (net (code "40") (name "DB6~{RST1}") (class "Default")
      (node (ref "DB6") (pin "4") (pinfunction "4_4") (pintype "passive"))
    )
    (net (code "41") (name "DB6~{RST2}") (class "Default")
      (node (ref "DB6") (pin "2") (pinfunction "2_2") (pintype "passive"))
    )
    (net (code "42") (name "DB7D") (class "Default")
      (node (ref "DB7") (pin "13") (pinfunction "13_13") (pintype "passive"))
    )
    (net (code "43") (name "DB7EN-MUX") (class "Default")
      (node (ref "DB7") (pin "10") (pinfunction "10_10") (pintype "passive"))
      (node (ref "Q13") (pin "3") (pinfunction "D_3") (pintype "passive"))
      (node (ref "R40") (pin "2") (pinfunction "2_2") (pintype "passive"))
    )
    (net (code "44") (name "DB7~{INT1}") (class "Default")
      (node (ref "DB7") (pin "8") (pinfunction "8_8") (pintype "passive"))
    )
    (net (code "45") (name "DB7~{INT2}") (class "Default")
      (node (ref "DB7") (pin "6") (pinfunction "6_6") (pintype "passive"))
    )
    (net (code "46") (name "DB7~{RST1}") (class "Default")
      (node (ref "DB7") (pin "4") (pinfunction "4_4") (pintype "passive"))
    )
    (net (code "47") (name "DB7~{RST2}") (class "Default")
      (node (ref "DB7") (pin "2") (pinfunction "2_2") (pintype "passive"))
    )
    (net (code "48") (name "DB8D") (class "Default")
      (node (ref "DB8") (pin "13") (pinfunction "13_13") (pintype "passive"))
    )
    (net (code "49") (name "DB8EN-MUX") (class "Default")
      (node (ref "DB8") (pin "10") (pinfunction "10_10") (pintype "passive"))
      (node (ref "Q14") (pin "3") (pinfunction "D_3") (pintype "passive"))
      (node (ref "R42") (pin "2") (pinfunction "2_2") (pintype "passive"))
    )
    (net (code "50") (name "DB8~{INT1}") (class "Default")
      (node (ref "DB8") (pin "8") (pinfunction "8_8") (pintype "passive"))
    )
    (net (code "51") (name "DB8~{INT2}") (class "Default")
      (node (ref "DB8") (pin "6") (pinfunction "6_6") (pintype "passive"))
    )
    (net (code "52") (name "DB8~{RST1}") (class "Default")
      (node (ref "DB8") (pin "4") (pinfunction "4_4") (pintype "passive"))
    )
    (net (code "53") (name "DB8~{RST2}") (class "Default")
      (node (ref "DB8") (pin "2") (pinfunction "2_2") (pintype "passive"))
    )
    (net (code "54") (name "GND") (class "Default")
      (node (ref "C1") (pin "C") (pinfunction "-_C") (pintype "passive"))
      (node (ref "C10") (pin "2") (pinfunction "2_2") (pintype "passive"))
      (node (ref "C11") (pin "C") (pinfunction "-_C") (pintype "passive"))
      (node (ref "C12") (pin "C") (pinfunction "-_C") (pintype "passive"))
      (node (ref "C13") (pin "2") (pinfunction "2_2") (pintype "passive"))
      (node (ref "C14") (pin "2") (pinfunction "2_2") (pintype "passive"))
      (node (ref "C15") (pin "2") (pinfunction "2_2") (pintype "passive"))
      (node (ref "C16") (pin "2") (pinfunction "2_2") (pintype "passive"))
      (node (ref "C17") (pin "C") (pinfunction "-_C") (pintype "passive"))
      (node (ref "C2") (pin "2") (pinfunction "2_2") (pintype "passive"))
      (node (ref "C22") (pin "2") (pinfunction "2_2") (pintype "passive"))
      (node (ref "C23") (pin "P$2") (pinfunction "-_P$2") (pintype "passive"))
      (node (ref "C24") (pin "C") (pinfunction "-_C") (pintype "passive"))
      (node (ref "C25") (pin "C") (pinfunction "-_C") (pintype "passive"))
      (node (ref "C26") (pin "2") (pinfunction "2_2") (pintype "passive"))
      (node (ref "C27") (pin "2") (pinfunction "2_2") (pintype "passive"))
      (node (ref "C3") (pin "2") (pinfunction "2_2") (pintype "passive"))
      (node (ref "C4") (pin "2") (pinfunction "2_2") (pintype "passive"))
      (node (ref "C5") (pin "2") (pinfunction "2_2") (pintype "passive"))
      (node (ref "C6") (pin "2") (pinfunction "2_2") (pintype "passive"))
      (node (ref "C7") (pin "2") (pinfunction "2_2") (pintype "passive"))
      (node (ref "C8") (pin "2") (pinfunction "2_2") (pintype "passive"))
      (node (ref "C9") (pin "2") (pinfunction "2_2") (pintype "passive"))
      (node (ref "CN1") (pin "GND") (pinfunction "GND_GND") (pintype "power_in"))
      (node (ref "DB1") (pin "17") (pinfunction "17_17") (pintype "passive"))
      (node (ref "DB1") (pin "19") (pinfunction "19_19") (pintype "passive"))
      (node (ref "DB2") (pin "17") (pinfunction "17_17") (pintype "passive"))
      (node (ref "DB2") (pin "19") (pinfunction "19_19") (pintype "passive"))
      (node (ref "DB3") (pin "17") (pinfunction "17_17") (pintype "passive"))
      (node (ref "DB3") (pin "19") (pinfunction "19_19") (pintype "passive"))
      (node (ref "DB4") (pin "17") (pinfunction "17_17") (pintype "passive"))
      (node (ref "DB4") (pin "19") (pinfunction "19_19") (pintype "passive"))
      (node (ref "DB5") (pin "17") (pinfunction "17_17") (pintype "passive"))
      (node (ref "DB5") (pin "19") (pinfunction "19_19") (pintype "passive"))
      (node (ref "DB6") (pin "17") (pinfunction "17_17") (pintype "passive"))
      (node (ref "DB6") (pin "19") (pinfunction "19_19") (pintype "passive"))
      (node (ref "DB7") (pin "17") (pinfunction "17_17") (pintype "passive"))
      (node (ref "DB7") (pin "19") (pinfunction "19_19") (pintype "passive"))
      (node (ref "DB8") (pin "17") (pinfunction "17_17") (pintype "passive"))
      (node (ref "DB8") (pin "19") (pinfunction "19_19") (pintype "passive"))
      (node (ref "IC1") (pin "3") (pinfunction "GND_3") (pintype "passive"))
      (node (ref "IC2") (pin "3") (pinfunction "GND_3") (pintype "passive"))
      (node (ref "JP10") (pin "GND") (pinfunction "6_GND") (pintype "passive"))
      (node (ref "JP11") (pin "1") (pinfunction "1_1") (pintype "passive"))
      (node (ref "JP14") (pin "1") (pinfunction "1_1") (pintype "passive"))
      (node (ref "JP15") (pin "1") (pinfunction "1_1") (pintype "passive"))
      (node (ref "JP9") (pin "GND") (pinfunction "6_GND") (pintype "passive"))
      (node (ref "LED1") (pin "C") (pinfunction "C_C") (pintype "passive"))
      (node (ref "LED2") (pin "C") (pinfunction "C_C") (pintype "passive"))
      (node (ref "Q3") (pin "2") (pinfunction "S_2") (pintype "passive"))
      (node (ref "Q4") (pin "2") (pinfunction "S_2") (pintype "passive"))
      (node (ref "Q5") (pin "2") (pinfunction "S_2") (pintype "passive"))
      (node (ref "Q6") (pin "2") (pinfunction "S_2") (pintype "passive"))
      (node (ref "R1") (pin "2") (pinfunction "2_2") (pintype "passive"))
      (node (ref "R15") (pin "1") (pinfunction "1_1") (pintype "passive"))
      (node (ref "R28") (pin "1") (pinfunction "1_1") (pintype "passive"))
      (node (ref "R30") (pin "1") (pinfunction "1_1") (pintype "passive"))
      (node (ref "R32") (pin "1") (pinfunction "1_1") (pintype "passive"))
      (node (ref "R34") (pin "1") (pinfunction "1_1") (pintype "passive"))
      (node (ref "R36") (pin "1") (pinfunction "1_1") (pintype "passive"))
      (node (ref "R38") (pin "1") (pinfunction "1_1") (pintype "passive"))
      (node (ref "R40") (pin "1") (pinfunction "1_1") (pintype "passive"))
      (node (ref "R42") (pin "1") (pinfunction "1_1") (pintype "passive"))
      (node (ref "R8") (pin "1") (pinfunction "1_1") (pintype "passive"))
      (node (ref "S1") (pin "3") (pinfunction "3_3") (pintype "passive"))
      (node (ref "S1") (pin "4") (pinfunction "4_4") (pintype "passive"))
      (node (ref "S2") (pin "3") (pinfunction "3_3") (pintype "passive"))
      (node (ref "S2") (pin "4") (pinfunction "4_4") (pintype "passive"))
      (node (ref "U$1") (pin "1") (pinfunction "GND_1") (pintype "bidirectional"))
      (node (ref "U$1") (pin "12") (pinfunction "GND1_12") (pintype "bidirectional"))
      (node (ref "U$1") (pin "28") (pinfunction "GND2_28") (pintype "bidirectional"))
      (node (ref "U$1") (pin "29") (pinfunction "GND3_29") (pintype "bidirectional"))
      (node (ref "U$10") (pin "1") (pinfunction "P$1_1") (pintype "bidirectional"))
      (node (ref "U$10") (pin "2") (pinfunction "P$1_2") (pintype "bidirectional"))
      (node (ref "U1") (pin "23") (pinfunction "GNDANA_23") (pintype "bidirectional"))
      (node (ref "U1") (pin "36") (pinfunction "GND_36") (pintype "bidirectional"))
      (node (ref "U1") (pin "6") (pinfunction "GND_6") (pintype "bidirectional"))
      (node (ref "U1") (pin "64") (pinfunction "GND_64") (pintype "bidirectional"))
      (node (ref "U2") (pin "4") (pinfunction "GND_4") (pintype "bidirectional"))
      (node (ref "U4") (pin "5") (pinfunction "GND2_5") (pintype "bidirectional"))
    )
    (net (code "55") (name "GNDIO") (class "Default")
      (node (ref "C18") (pin "2") (pinfunction "2_2") (pintype "passive"))
      (node (ref "C19") (pin "C") (pinfunction "-_C") (pintype "passive"))
      (node (ref "C20") (pin "2") (pinfunction "2_2") (pintype "passive"))
      (node (ref "C21") (pin "2") (pinfunction "2_2") (pintype "passive"))
      (node (ref "JP12") (pin "4") (pinfunction "4_4") (pintype "passive"))
      (node (ref "U3") (pin "18") (pinfunction "GND2_18") (pintype "power_in"))
      (node (ref "U3") (pin "21") (pinfunction "GND3_21") (pintype "power_in"))
      (node (ref "U3") (pin "25") (pinfunction "AGND_25") (pintype "power_in"))
      (node (ref "U3") (pin "26") (pinfunction "TEST_26") (pintype "input"))
      (node (ref "U3") (pin "7") (pinfunction "GND1_7") (pintype "power_in"))
      (node (ref "U4") (pin "4") (pinfunction "GND1_4") (pintype "bidirectional"))
    )
    (net (code "56") (name "I2C-CLK") (class "Default")
      (node (ref "JP8") (pin "3") (pinfunction "3_3") (pintype "passive"))
      (node (ref "R49") (pin "1") (pinfunction "1_1") (pintype "passive"))
      (node (ref "U1") (pin "60") (pinfunction "PA24_60") (pintype "bidirectional"))
      (node (ref "U2") (pin "2") (pinfunction "SCLA_2") (pintype "bidirectional"))
    )
    (net (code "57") (name "I2C-DAT") (class "Default")
      (node (ref "JP7") (pin "1") (pinfunction "1_1") (pintype "passive"))
      (node (ref "R48") (pin "1") (pinfunction "1_1") (pintype "passive"))
      (node (ref "U1") (pin "59") (pinfunction "PA23_59") (pintype "bidirectional"))
      (node (ref "U2") (pin "3") (pinfunction "SDAA_3") (pintype "bidirectional"))
    )
    (net (code "58") (name "M0") (class "Default")
      (node (ref "JP4") (pin "4") (pinfunction "4_4") (pintype "passive"))
      (node (ref "R16") (pin "1") (pinfunction "1_1") (pintype "passive"))
      (node (ref "U1") (pin "16") (pinfunction "PA05_16") (pintype "bidirectional"))
    )
    (net (code "59") (name "M0E1") (class "Default")
      (node (ref "JP3") (pin "8") (pinfunction "8_8") (pintype "passive"))
      (node (ref "R29") (pin "1") (pinfunction "1_1") (pintype "passive"))
      (node (ref "U1") (pin "22") (pinfunction "PA07_22") (pintype "bidirectional"))
    )
    (net (code "60") (name "M0E2") (class "Default")
      (node (ref "JP3") (pin "7") (pinfunction "7_7") (pintype "passive"))
      (node (ref "R31") (pin "1") (pinfunction "1_1") (pintype "passive"))
      (node (ref "U1") (pin "26") (pinfunction "PA08_26") (pintype "bidirectional"))
    )
    (net (code "61") (name "M0E3") (class "Default")
      (node (ref "JP3") (pin "6") (pinfunction "6_6") (pintype "passive"))
      (node (ref "R33") (pin "1") (pinfunction "1_1") (pintype "passive"))
      (node (ref "U1") (pin "27") (pinfunction "PB06_27") (pintype "bidirectional"))
    )
    (net (code "62") (name "M0E4") (class "Default")
      (node (ref "JP3") (pin "5") (pinfunction "5_5") (pintype "passive"))
      (node (ref "R35") (pin "1") (pinfunction "1_1") (pintype "passive"))
      (node (ref "U1") (pin "28") (pinfunction "PB07_28") (pintype "bidirectional"))
    )
    (net (code "63") (name "M0E5") (class "Default")
      (node (ref "JP3") (pin "4") (pinfunction "4_4") (pintype "passive"))
      (node (ref "R37") (pin "1") (pinfunction "1_1") (pintype "passive"))
      (node (ref "U1") (pin "29") (pinfunction "PA09_29") (pintype "bidirectional"))
    )
    (net (code "64") (name "M0E6") (class "Default")
      (node (ref "JP3") (pin "3") (pinfunction "3_3") (pintype "passive"))
      (node (ref "R39") (pin "1") (pinfunction "1_1") (pintype "passive"))
      (node (ref "U1") (pin "30") (pinfunction "PA10_30") (pintype "bidirectional"))
    )
    (net (code "65") (name "M0E7") (class "Default")
      (node (ref "JP3") (pin "2") (pinfunction "2_2") (pintype "passive"))
      (node (ref "R41") (pin "1") (pinfunction "1_1") (pintype "passive"))
      (node (ref "U1") (pin "31") (pinfunction "PA11_31") (pintype "bidirectional"))
    )
    (net (code "66") (name "M0E8") (class "Default")
      (node (ref "JP3") (pin "1") (pinfunction "1_1") (pintype "passive"))
      (node (ref "R43") (pin "1") (pinfunction "1_1") (pintype "passive"))
      (node (ref "U1") (pin "32") (pinfunction "PA12_32") (pintype "bidirectional"))
    )
    (net (code "67") (name "M1") (class "Default")
      (node (ref "JP4") (pin "3") (pinfunction "3_3") (pintype "passive"))
      (node (ref "R19") (pin "1") (pinfunction "1_1") (pintype "passive"))
      (node (ref "U1") (pin "19") (pinfunction "PB04_19") (pintype "bidirectional"))
    )
    (net (code "68") (name "M2") (class "Default")
      (node (ref "JP4") (pin "2") (pinfunction "2_2") (pintype "passive"))
      (node (ref "R22") (pin "1") (pinfunction "1_1") (pintype "passive"))
      (node (ref "U1") (pin "20") (pinfunction "PB05_20") (pintype "bidirectional"))
    )
    (net (code "69") (name "M3") (class "Default")
      (node (ref "JP4") (pin "1") (pinfunction "1_1") (pintype "passive"))
      (node (ref "R25") (pin "1") (pinfunction "1_1") (pintype "passive"))
      (node (ref "U1") (pin "21") (pinfunction "PA06_21") (pintype "bidirectional"))
    )
    (net (code "70") (name "MUX-A0") (class "Default")
      (node (ref "DB1") (pin "14") (pinfunction "14_14") (pintype "passive"))
      (node (ref "DB2") (pin "14") (pinfunction "14_14") (pintype "passive"))
      (node (ref "DB3") (pin "14") (pinfunction "14_14") (pintype "passive"))
      (node (ref "DB4") (pin "14") (pinfunction "14_14") (pintype "passive"))
      (node (ref "DB5") (pin "14") (pinfunction "14_14") (pintype "passive"))
      (node (ref "DB6") (pin "14") (pinfunction "14_14") (pintype "passive"))
      (node (ref "DB7") (pin "14") (pinfunction "14_14") (pintype "passive"))
      (node (ref "DB8") (pin "14") (pinfunction "14_14") (pintype "passive"))
      (node (ref "M-A0") (pin "C") (pinfunction "C_C") (pintype "passive"))
      (node (ref "Q3") (pin "3") (pinfunction "D_3") (pintype "passive"))
      (node (ref "R17") (pin "1") (pinfunction "1_1") (pintype "passive"))
      (node (ref "U$4") (pin "1") (pinfunction "P$1_1") (pintype "bidirectional"))
      (node (ref "U$4") (pin "2") (pinfunction "P$1_2") (pintype "bidirectional"))
    )
    (net (code "71") (name "MUX-A1") (class "Default")
      (node (ref "DB1") (pin "16") (pinfunction "16_16") (pintype "passive"))
      (node (ref "DB2") (pin "16") (pinfunction "16_16") (pintype "passive"))
      (node (ref "DB3") (pin "16") (pinfunction "16_16") (pintype "passive"))
      (node (ref "DB4") (pin "16") (pinfunction "16_16") (pintype "passive"))
      (node (ref "DB5") (pin "16") (pinfunction "16_16") (pintype "passive"))
      (node (ref "DB6") (pin "16") (pinfunction "16_16") (pintype "passive"))
      (node (ref "DB7") (pin "16") (pinfunction "16_16") (pintype "passive"))
      (node (ref "DB8") (pin "16") (pinfunction "16_16") (pintype "passive"))
      (node (ref "M-A1") (pin "C") (pinfunction "C_C") (pintype "passive"))
      (node (ref "Q4") (pin "3") (pinfunction "D_3") (pintype "passive"))
      (node (ref "R20") (pin "1") (pinfunction "1_1") (pintype "passive"))
      (node (ref "U$5") (pin "1") (pinfunction "P$1_1") (pintype "bidirectional"))
      (node (ref "U$5") (pin "2") (pinfunction "P$1_2") (pintype "bidirectional"))
    )
    (net (code "72") (name "MUX-A2") (class "Default")
      (node (ref "DB1") (pin "18") (pinfunction "18_18") (pintype "passive"))
      (node (ref "DB2") (pin "18") (pinfunction "18_18") (pintype "passive"))
      (node (ref "DB3") (pin "18") (pinfunction "18_18") (pintype "passive"))
      (node (ref "DB4") (pin "18") (pinfunction "18_18") (pintype "passive"))
      (node (ref "DB5") (pin "18") (pinfunction "18_18") (pintype "passive"))
      (node (ref "DB6") (pin "18") (pinfunction "18_18") (pintype "passive"))
      (node (ref "DB7") (pin "18") (pinfunction "18_18") (pintype "passive"))
      (node (ref "DB8") (pin "18") (pinfunction "18_18") (pintype "passive"))
      (node (ref "M-A2") (pin "C") (pinfunction "C_C") (pintype "passive"))
      (node (ref "Q5") (pin "3") (pinfunction "D_3") (pintype "passive"))
      (node (ref "R23") (pin "1") (pinfunction "1_1") (pintype "passive"))
      (node (ref "U$6") (pin "1") (pinfunction "P$1_1") (pintype "bidirectional"))
      (node (ref "U$6") (pin "2") (pinfunction "P$1_2") (pintype "bidirectional"))
    )
    (net (code "73") (name "MUX-A3") (class "Default")
      (node (ref "DB1") (pin "20") (pinfunction "20_20") (pintype "passive"))
      (node (ref "DB2") (pin "20") (pinfunction "20_20") (pintype "passive"))
      (node (ref "DB3") (pin "20") (pinfunction "20_20") (pintype "passive"))
      (node (ref "DB4") (pin "20") (pinfunction "20_20") (pintype "passive"))
      (node (ref "DB5") (pin "20") (pinfunction "20_20") (pintype "passive"))
      (node (ref "DB6") (pin "20") (pinfunction "20_20") (pintype "passive"))
      (node (ref "DB7") (pin "20") (pinfunction "20_20") (pintype "passive"))
      (node (ref "DB8") (pin "20") (pinfunction "20_20") (pintype "passive"))
      (node (ref "M-A3") (pin "C") (pinfunction "C_C") (pintype "passive"))
      (node (ref "Q6") (pin "3") (pinfunction "D_3") (pintype "passive"))
      (node (ref "R26") (pin "1") (pinfunction "1_1") (pintype "passive"))
      (node (ref "U$7") (pin "1") (pinfunction "P$1_1") (pintype "bidirectional"))
      (node (ref "U$7") (pin "2") (pinfunction "P$1_2") (pintype "bidirectional"))
    )
    (net (code "74") (name "MUX-OUT") (class "Default")
      (node (ref "DB1") (pin "12") (pinfunction "12_12") (pintype "passive"))
      (node (ref "DB2") (pin "12") (pinfunction "12_12") (pintype "passive"))
      (node (ref "DB3") (pin "12") (pinfunction "12_12") (pintype "passive"))
      (node (ref "DB4") (pin "12") (pinfunction "12_12") (pintype "passive"))
      (node (ref "DB5") (pin "12") (pinfunction "12_12") (pintype "passive"))
      (node (ref "DB6") (pin "12") (pinfunction "12_12") (pintype "passive"))
      (node (ref "DB7") (pin "12") (pinfunction "12_12") (pintype "passive"))
      (node (ref "DB8") (pin "12") (pinfunction "12_12") (pintype "passive"))
      (node (ref "Q15") (pin "3") (pinfunction "D_3") (pintype "passive"))
      (node (ref "R47") (pin "1") (pinfunction "1_1") (pintype "passive"))
      (node (ref "U$13") (pin "1") (pinfunction "P$1_1") (pintype "bidirectional"))
      (node (ref "U$13") (pin "2") (pinfunction "P$1_2") (pintype "bidirectional"))
    )
    (net (code "75") (name "MUX-OUT-LV") (class "Default")
      (node (ref "JP4") (pin "5") (pinfunction "5_5") (pintype "passive"))
      (node (ref "Q15") (pin "2") (pinfunction "S_2") (pintype "passive"))
      (node (ref "R46") (pin "1") (pinfunction "1_1") (pintype "passive"))
      (node (ref "U1") (pin "15") (pinfunction "PA04_15") (pintype "bidirectional"))
    )
    (net (code "76") (name "Net-(C1-+)") (class "Default")
      (node (ref "C1") (pin "A") (pinfunction "+_A") (pintype "passive"))
      (node (ref "C13") (pin "1") (pinfunction "1_1") (pintype "passive"))
      (node (ref "L1") (pin "1") (pinfunction "1_1") (pintype "passive"))
      (node (ref "U1") (pin "5") (pinfunction "VDDCORE_5") (pintype "bidirectional"))
    )
    (net (code "77") (name "Net-(C12-+)") (class "Default")
      (node (ref "C10") (pin "1") (pinfunction "1_1") (pintype "passive"))
      (node (ref "C12") (pin "A") (pinfunction "+_A") (pintype "passive"))
      (node (ref "L2") (pin "2") (pinfunction "2_2") (pintype "passive"))
      (node (ref "U1") (pin "25") (pinfunction "VDDANA_25") (pintype "bidirectional"))
    )
    (net (code "78") (name "Net-(C16-Pad1)") (class "Default")
      (node (ref "C16") (pin "1") (pinfunction "1_1") (pintype "passive"))
      (node (ref "JP13") (pin "1") (pinfunction "1_1") (pintype "passive"))
      (node (ref "R10") (pin "2") (pinfunction "2_2") (pintype "passive"))
      (node (ref "R9") (pin "1") (pinfunction "1_1") (pintype "passive"))
    )
    (net (code "79") (name "Net-(C19-+)") (class "Default")
      (node (ref "C19") (pin "A") (pinfunction "+_A") (pintype "passive"))
      (node (ref "C20") (pin "1") (pinfunction "1_1") (pintype "passive"))
      (node (ref "C21") (pin "1") (pinfunction "1_1") (pintype "passive"))
      (node (ref "JP12") (pin "1") (pinfunction "1_1") (pintype "passive"))
      (node (ref "R44") (pin "2") (pinfunction "2_2") (pintype "passive"))
      (node (ref "R45") (pin "2") (pinfunction "2_2") (pintype "passive"))
      (node (ref "U3") (pin "20") (pinfunction "VCC_20") (pintype "power_in"))
      (node (ref "U3") (pin "4") (pinfunction "VCCIO_4") (pintype "power_in"))
      (node (ref "U4") (pin "1") (pinfunction "VCC1_1") (pintype "bidirectional"))
    )
    (net (code "80") (name "Net-(C23-+)") (class "Default")
      (node (ref "C23") (pin "P$1") (pinfunction "+_P$1") (pintype "passive"))
      (node (ref "D1") (pin "C") (pinfunction "C_C") (pintype "passive"))
      (node (ref "IC1") (pin "1") (pinfunction "VI_1") (pintype "input"))
      (node (ref "IC2") (pin "1") (pinfunction "VI_1") (pintype "input"))
      (node (ref "U$11") (pin "1") (pinfunction "P$1_1") (pintype "bidirectional"))
      (node (ref "U$11") (pin "2") (pinfunction "P$1_2") (pintype "bidirectional"))
    )
    (net (code "81") (name "Net-(CN1-PadD+)") (class "Default")
      (node (ref "CN1") (pin "D+") (pinfunction "D+_D+") (pintype "bidirectional"))
      (node (ref "R5") (pin "1") (pinfunction "1_1") (pintype "passive"))
    )
    (net (code "82") (name "Net-(CN1-PadD-)") (class "Default")
      (node (ref "CN1") (pin "D-") (pinfunction "D-_D-") (pintype "bidirectional"))
      (node (ref "R6") (pin "1") (pinfunction "1_1") (pintype "passive"))
    )
    (net (code "83") (name "Net-(D1-PadA)") (class "Default")
      (node (ref "D1") (pin "A") (pinfunction "A_A") (pintype "passive"))
      (node (ref "JP11") (pin "2") (pinfunction "2_2") (pintype "passive"))
    )
    (net (code "84") (name "Net-(JP1-1)") (class "Default")
      (node (ref "C14") (pin "1") (pinfunction "1_1") (pintype "passive"))
      (node (ref "JP1") (pin "P$1") (pinfunction "1_P$1") (pintype "passive"))
      (node (ref "U1") (pin "24") (pinfunction "ADVREFP_24") (pintype "bidirectional"))
    )
    (net (code "85") (name "Net-(LED1-PadA)") (class "Default")
      (node (ref "LED1") (pin "A") (pinfunction "A_A") (pintype "passive"))
      (node (ref "R14") (pin "1") (pinfunction "1_1") (pintype "passive"))
    )
    (net (code "86") (name "Net-(LED2-PadA)") (class "Default")
      (node (ref "LED2") (pin "A") (pinfunction "A_A") (pintype "passive"))
      (node (ref "R13") (pin "1") (pinfunction "1_1") (pintype "passive"))
    )
    (net (code "87") (name "Net-(M-A0-PadA)") (class "Default")
      (node (ref "M-A0") (pin "A") (pinfunction "A_A") (pintype "passive"))
      (node (ref "R18") (pin "1") (pinfunction "1_1") (pintype "passive"))
    )
    (net (code "88") (name "Net-(M-A1-PadA)") (class "Default")
      (node (ref "M-A1") (pin "A") (pinfunction "A_A") (pintype "passive"))
      (node (ref "R21") (pin "1") (pinfunction "1_1") (pintype "passive"))
    )
    (net (code "89") (name "Net-(M-A2-PadA)") (class "Default")
      (node (ref "M-A2") (pin "A") (pinfunction "A_A") (pintype "passive"))
      (node (ref "R24") (pin "1") (pinfunction "1_1") (pintype "passive"))
    )
    (net (code "90") (name "Net-(M-A3-PadA)") (class "Default")
      (node (ref "M-A3") (pin "A") (pinfunction "A_A") (pintype "passive"))
      (node (ref "R27") (pin "1") (pinfunction "1_1") (pintype "passive"))
    )
    (net (code "91") (name "Net-(Q1-2)") (class "Default")
      (node (ref "C8") (pin "1") (pinfunction "1_1") (pintype "passive"))
      (node (ref "Q1") (pin "4") (pinfunction "2_4") (pintype "passive"))
      (node (ref "U1") (pin "18") (pinfunction "XOUT32_18") (pintype "bidirectional"))
    )
    (net (code "92") (name "Net-(Q2-2)") (class "Default")
      (node (ref "C5") (pin "1") (pinfunction "1_1") (pintype "passive"))
      (node (ref "Q2") (pin "3") (pinfunction "2_3") (pintype "passive"))
      (node (ref "U1") (pin "1") (pinfunction "PA00_1") (pintype "bidirectional"))
    )
    (net (code "93") (name "Net-(Q3-G)") (class "Default")
      (node (ref "Q3") (pin "1") (pinfunction "G_1") (pintype "passive"))
      (node (ref "R16") (pin "2") (pinfunction "2_2") (pintype "passive"))
    )
    (net (code "94") (name "Net-(Q4-G)") (class "Default")
      (node (ref "Q4") (pin "1") (pinfunction "G_1") (pintype "passive"))
      (node (ref "R19") (pin "2") (pinfunction "2_2") (pintype "passive"))
    )
    (net (code "95") (name "Net-(Q5-G)") (class "Default")
      (node (ref "Q5") (pin "1") (pinfunction "G_1") (pintype "passive"))
      (node (ref "R22") (pin "2") (pinfunction "2_2") (pintype "passive"))
    )
    (net (code "96") (name "Net-(Q6-G)") (class "Default")
      (node (ref "Q6") (pin "1") (pinfunction "G_1") (pintype "passive"))
      (node (ref "R25") (pin "2") (pinfunction "2_2") (pintype "passive"))
    )
    (net (code "97") (name "Net-(Q7-G)") (class "Default")
      (node (ref "Q7") (pin "1") (pinfunction "G_1") (pintype "passive"))
      (node (ref "R29") (pin "2") (pinfunction "2_2") (pintype "passive"))
    )
    (net (code "98") (name "Net-(Q8-G)") (class "Default")
      (node (ref "Q8") (pin "1") (pinfunction "G_1") (pintype "passive"))
      (node (ref "R31") (pin "2") (pinfunction "2_2") (pintype "passive"))
    )
    (net (code "99") (name "Net-(Q9-G)") (class "Default")
      (node (ref "Q9") (pin "1") (pinfunction "G_1") (pintype "passive"))
      (node (ref "R33") (pin "2") (pinfunction "2_2") (pintype "passive"))
    )
    (net (code "100") (name "Net-(Q10-G)") (class "Default")
      (node (ref "Q10") (pin "1") (pinfunction "G_1") (pintype "passive"))
      (node (ref "R35") (pin "2") (pinfunction "2_2") (pintype "passive"))
    )
    (net (code "101") (name "Net-(Q11-G)") (class "Default")
      (node (ref "Q11") (pin "1") (pinfunction "G_1") (pintype "passive"))
      (node (ref "R37") (pin "2") (pinfunction "2_2") (pintype "passive"))
    )
    (net (code "102") (name "Net-(Q12-G)") (class "Default")
      (node (ref "Q12") (pin "1") (pinfunction "G_1") (pintype "passive"))
      (node (ref "R39") (pin "2") (pinfunction "2_2") (pintype "passive"))
    )
    (net (code "103") (name "Net-(Q13-G)") (class "Default")
      (node (ref "Q13") (pin "1") (pinfunction "G_1") (pintype "passive"))
      (node (ref "R41") (pin "2") (pinfunction "2_2") (pintype "passive"))
    )
    (net (code "104") (name "Net-(Q14-G)") (class "Default")
      (node (ref "Q14") (pin "1") (pinfunction "G_1") (pintype "passive"))
      (node (ref "R43") (pin "2") (pinfunction "2_2") (pintype "passive"))
    )
    (net (code "105") (name "Net-(R1-Pad1)") (class "Default")
      (node (ref "R1") (pin "1") (pinfunction "1_1") (pintype "passive"))
      (node (ref "SJ1") (pin "3") (pinfunction "3_3") (pintype "passive"))
    )
    (net (code "106") (name "Net-(R2-Pad1)") (class "Default")
      (node (ref "R2") (pin "1") (pinfunction "1_1") (pintype "passive"))
      (node (ref "SJ1") (pin "1") (pinfunction "1_1") (pintype "passive"))
    )
    (net (code "107") (name "Net-(R4-Pad1)") (class "Default")
      (node (ref "R4") (pin "1") (pinfunction "1_1") (pintype "passive"))
      (node (ref "S1") (pin "1") (pinfunction "1_1") (pintype "passive"))
      (node (ref "S1") (pin "2") (pinfunction "2_2") (pintype "passive"))
    )
    (net (code "108") (name "Net-(R10-Pad1)") (class "Default")
      (node (ref "R10") (pin "1") (pinfunction "1_1") (pintype "passive"))
      (node (ref "S2") (pin "1") (pinfunction "1_1") (pintype "passive"))
      (node (ref "S2") (pin "2") (pinfunction "2_2") (pintype "passive"))
    )
    (net (code "109") (name "Net-(R44-Pad1)") (class "Default")
      (node (ref "R44") (pin "1") (pinfunction "1_1") (pintype "passive"))
      (node (ref "TX") (pin "A") (pinfunction "A_A") (pintype "passive"))
    )
    (net (code "110") (name "Net-(R45-Pad1)") (class "Default")
      (node (ref "R45") (pin "1") (pinfunction "1_1") (pintype "passive"))
      (node (ref "RX") (pin "A") (pinfunction "A_A") (pintype "passive"))
    )
    (net (code "111") (name "Net-(U$1-PIO2)") (class "Default")
      (node (ref "R13") (pin "2") (pinfunction "2_2") (pintype "passive"))
      (node (ref "U$1") (pin "19") (pinfunction "PIO2_19") (pintype "bidirectional"))
    )
    (net (code "112") (name "Net-(U$1-PIO4)") (class "Default")
      (node (ref "R15") (pin "2") (pinfunction "2_2") (pintype "passive"))
      (node (ref "U$1") (pin "22") (pinfunction "PIO4_22") (pintype "bidirectional"))
    )
    (net (code "113") (name "Net-(U$1-PIO5)") (class "Default")
      (node (ref "R14") (pin "2") (pinfunction "2_2") (pintype "passive"))
      (node (ref "U$1") (pin "21") (pinfunction "PIO5_21") (pintype "bidirectional"))
    )
    (net (code "114") (name "Net-(U1-PA01)") (class "Default")
      (node (ref "C6") (pin "1") (pinfunction "1_1") (pintype "passive"))
      (node (ref "Q2") (pin "1") (pinfunction "1_1") (pintype "passive"))
      (node (ref "U1") (pin "2") (pinfunction "PA01_2") (pintype "bidirectional"))
    )
    (net (code "115") (name "Net-(U1-PA02)") (class "Default")
      (node (ref "SJ1") (pin "2") (pinfunction "2_2") (pintype "passive"))
      (node (ref "U1") (pin "3") (pinfunction "PA02_3") (pintype "bidirectional"))
    )
    (net (code "116") (name "Net-(U1-PA03)") (class "Default")
      (node (ref "JP6") (pin "2") (pinfunction "2_2") (pintype "passive"))
      (node (ref "U1") (pin "10") (pinfunction "PA03_10") (pintype "bidirectional"))
    )
    (net (code "117") (name "Net-(U1-PA13)") (class "Default")
      (node (ref "JP2") (pin "3") (pinfunction "3_3") (pintype "passive"))
      (node (ref "U1") (pin "40") (pinfunction "PA13_40") (pintype "bidirectional"))
    )
    (net (code "118") (name "Net-(U1-PA14)") (class "Default")
      (node (ref "JP2") (pin "2") (pinfunction "2_2") (pintype "passive"))
      (node (ref "U1") (pin "41") (pinfunction "PA14_41") (pintype "bidirectional"))
    )
    (net (code "119") (name "Net-(U1-PA15)") (class "Default")
      (node (ref "JP2") (pin "1") (pinfunction "1_1") (pintype "passive"))
      (node (ref "U1") (pin "42") (pinfunction "PA15_42") (pintype "bidirectional"))
    )
    (net (code "120") (name "Net-(U1-PA16)") (class "Default")
      (node (ref "JP5") (pin "8") (pinfunction "8_8") (pintype "passive"))
      (node (ref "U1") (pin "43") (pinfunction "PA16_43") (pintype "bidirectional"))
    )
    (net (code "121") (name "Net-(U1-PA17)") (class "Default")
      (node (ref "JP5") (pin "7") (pinfunction "7_7") (pintype "passive"))
      (node (ref "U1") (pin "44") (pinfunction "PA17_44") (pintype "bidirectional"))
    )
    (net (code "122") (name "Net-(U1-PA18)") (class "Default")
      (node (ref "JP5") (pin "2") (pinfunction "2_2") (pintype "passive"))
      (node (ref "U1") (pin "49") (pinfunction "PA18_49") (pintype "bidirectional"))
    )
    (net (code "123") (name "Net-(U1-PA19)") (class "Default")
      (node (ref "JP5") (pin "1") (pinfunction "1_1") (pintype "passive"))
      (node (ref "U1") (pin "50") (pinfunction "PA19_50") (pintype "bidirectional"))
    )
    (net (code "124") (name "Net-(U1-PA20)") (class "Default")
      (node (ref "JP7") (pin "8") (pinfunction "8_8") (pintype "passive"))
      (node (ref "U1") (pin "51") (pinfunction "PA20_51") (pintype "bidirectional"))
    )
    (net (code "125") (name "Net-(U1-PA25)") (class "Default")
      (node (ref "JP8") (pin "2") (pinfunction "2_2") (pintype "passive"))
      (node (ref "R6") (pin "2") (pinfunction "2_2") (pintype "passive"))
      (node (ref "U1") (pin "62") (pinfunction "PA25_62") (pintype "bidirectional"))
    )
    (net (code "126") (name "Net-(U1-PA26)") (class "Default")
      (node (ref "JP8") (pin "1") (pinfunction "1_1") (pintype "passive"))
      (node (ref "R5") (pin "2") (pinfunction "2_2") (pintype "passive"))
      (node (ref "U1") (pin "63") (pinfunction "PA26_63") (pintype "bidirectional"))
    )
    (net (code "127") (name "Net-(U1-PA27)") (class "Default")
      (node (ref "C26") (pin "1") (pinfunction "1_1") (pintype "passive"))
      (node (ref "JP15") (pin "2") (pinfunction "2_2") (pintype "passive"))
      (node (ref "JP2") (pin "8") (pinfunction "8_8") (pintype "passive"))
      (node (ref "R52") (pin "1") (pinfunction "1_1") (pintype "passive"))
      (node (ref "U1") (pin "33") (pinfunction "PA27_33") (pintype "bidirectional"))
    )
    (net (code "128") (name "Net-(U1-PA28)") (class "Default")
      (node (ref "C27") (pin "1") (pinfunction "1_1") (pintype "passive"))
      (node (ref "JP14") (pin "2") (pinfunction "2_2") (pintype "passive"))
      (node (ref "JP2") (pin "7") (pinfunction "7_7") (pintype "passive"))
      (node (ref "R53") (pin "1") (pinfunction "1_1") (pintype "passive"))
      (node (ref "U1") (pin "34") (pinfunction "PA28_34") (pintype "bidirectional"))
    )
    (net (code "129") (name "Net-(U1-PA29)") (class "Default")
      (node (ref "JP2") (pin "6") (pinfunction "6_6") (pintype "passive"))
      (node (ref "U1") (pin "35") (pinfunction "PA29_35") (pintype "bidirectional"))
    )
    (net (code "130") (name "Net-(U1-PA30)") (class "Default")
      (node (ref "JP2") (pin "5") (pinfunction "5_5") (pintype "passive"))
      (node (ref "U1") (pin "38") (pinfunction "PA30_38") (pintype "bidirectional"))
    )
    (net (code "131") (name "Net-(U1-PA31)") (class "Default")
      (node (ref "JP2") (pin "4") (pinfunction "4_4") (pintype "passive"))
      (node (ref "U1") (pin "39") (pinfunction "PA31_39") (pintype "bidirectional"))
    )
    (net (code "132") (name "Net-(U1-PB02)") (class "Default")
      (node (ref "JP4") (pin "7") (pinfunction "7_7") (pintype "passive"))
      (node (ref "U1") (pin "13") (pinfunction "PB02_13") (pintype "bidirectional"))
    )
    (net (code "133") (name "Net-(U1-PB03)") (class "Default")
      (node (ref "JP4") (pin "6") (pinfunction "6_6") (pintype "passive"))
      (node (ref "U1") (pin "14") (pinfunction "PB03_14") (pintype "bidirectional"))
    )
    (net (code "134") (name "Net-(U1-PB08)") (class "Default")
      (node (ref "JP5") (pin "6") (pinfunction "6_6") (pintype "passive"))
      (node (ref "U1") (pin "45") (pinfunction "PB08_45") (pintype "bidirectional"))
    )
    (net (code "135") (name "Net-(U1-PB11)") (class "Default")
      (node (ref "JP5") (pin "3") (pinfunction "3_3") (pintype "passive"))
      (node (ref "U1") (pin "48") (pinfunction "PB11_48") (pintype "bidirectional"))
    )
    (net (code "136") (name "Net-(U1-PB12)") (class "Default")
      (node (ref "JP7") (pin "7") (pinfunction "7_7") (pintype "passive"))
      (node (ref "U1") (pin "53") (pinfunction "PB12_53") (pintype "bidirectional"))
    )
    (net (code "137") (name "Net-(U1-PB13)") (class "Default")
      (node (ref "JP7") (pin "6") (pinfunction "6_6") (pintype "passive"))
      (node (ref "U1") (pin "54") (pinfunction "PB13_54") (pintype "bidirectional"))
    )
    (net (code "138") (name "Net-(U1-RESET_N)") (class "Default")
      (node (ref "C15") (pin "1") (pinfunction "1_1") (pintype "passive"))
      (node (ref "R3") (pin "1") (pinfunction "1_1") (pintype "passive"))
      (node (ref "R4") (pin "2") (pinfunction "2_2") (pintype "passive"))
      (node (ref "U1") (pin "4") (pinfunction "RESET_N_4") (pintype "bidirectional"))
    )
    (net (code "139") (name "Net-(U1-TCK)") (class "Default")
      (node (ref "JP6") (pin "3") (pinfunction "3_3") (pintype "passive"))
      (node (ref "U1") (pin "9") (pinfunction "TCK_9") (pintype "bidirectional"))
    )
    (net (code "140") (name "Net-(U1-VDDOUT\\)") (class "Default")
      (node (ref "L1") (pin "2") (pinfunction "2_2") (pintype "passive"))
      (node (ref "U1") (pin "7") (pinfunction "VDDOUT\\_7") (pintype "bidirectional"))
    )
    (net (code "141") (name "Net-(U1-XIN32)") (class "Default")
      (node (ref "C7") (pin "1") (pinfunction "1_1") (pintype "passive"))
      (node (ref "Q1") (pin "1") (pinfunction "1_1") (pintype "passive"))
      (node (ref "U1") (pin "17") (pinfunction "XIN32_17") (pintype "bidirectional"))
    )
    (net (code "142") (name "Net-(U3-RXD)") (class "Default")
      (node (ref "U3") (pin "5") (pinfunction "RXD_5") (pintype "input"))
      (node (ref "U4") (pin "2") (pinfunction "OUTA_2") (pintype "bidirectional"))
    )
    (net (code "143") (name "Net-(U3-RXLED)") (class "Default")
      (node (ref "RX") (pin "C") (pinfunction "C_C") (pintype "passive"))
      (node (ref "U3") (pin "22") (pinfunction "RXLED_22") (pintype "bidirectional"))
    )
    (net (code "144") (name "Net-(U3-TXD)") (class "Default")
      (node (ref "U3") (pin "1") (pinfunction "TXD_1") (pintype "output"))
      (node (ref "U4") (pin "3") (pinfunction "INB_3") (pintype "bidirectional"))
    )
    (net (code "145") (name "Net-(U3-TXLED)") (class "Default")
      (node (ref "TX") (pin "C") (pinfunction "C_C") (pintype "passive"))
      (node (ref "U3") (pin "23") (pinfunction "TXLED_23") (pintype "bidirectional"))
    )
    (net (code "146") (name "Net-(U3-USBDM)") (class "Default")
      (node (ref "JP12") (pin "2") (pinfunction "2_2") (pintype "passive"))
      (node (ref "U3") (pin "16") (pinfunction "USBDM_16") (pintype "bidirectional"))
    )
    (net (code "147") (name "Net-(U3-USBDP)") (class "Default")
      (node (ref "JP12") (pin "3") (pinfunction "3_3") (pintype "passive"))
      (node (ref "U3") (pin "15") (pinfunction "USBDP_15") (pintype "bidirectional"))
    )
    (net (code "148") (name "SCL") (class "Default")
      (node (ref "DB1") (pin "5") (pinfunction "5_5") (pintype "passive"))
      (node (ref "DB2") (pin "5") (pinfunction "5_5") (pintype "passive"))
      (node (ref "DB3") (pin "5") (pinfunction "5_5") (pintype "passive"))
      (node (ref "DB4") (pin "5") (pinfunction "5_5") (pintype "passive"))
      (node (ref "DB5") (pin "5") (pinfunction "5_5") (pintype "passive"))
      (node (ref "DB6") (pin "5") (pinfunction "5_5") (pintype "passive"))
      (node (ref "DB7") (pin "5") (pinfunction "5_5") (pintype "passive"))
      (node (ref "DB8") (pin "5") (pinfunction "5_5") (pintype "passive"))
      (node (ref "R50") (pin "1") (pinfunction "1_1") (pintype "passive"))
      (node (ref "U$2") (pin "1") (pinfunction "P$1_1") (pintype "bidirectional"))
      (node (ref "U$2") (pin "2") (pinfunction "P$1_2") (pintype "bidirectional"))
      (node (ref "U2") (pin "7") (pinfunction "SCLB_7") (pintype "bidirectional"))
    )
    (net (code "149") (name "SDA") (class "Default")
      (node (ref "DB1") (pin "7") (pinfunction "7_7") (pintype "passive"))
      (node (ref "DB2") (pin "7") (pinfunction "7_7") (pintype "passive"))
      (node (ref "DB3") (pin "7") (pinfunction "7_7") (pintype "passive"))
      (node (ref "DB4") (pin "7") (pinfunction "7_7") (pintype "passive"))
      (node (ref "DB5") (pin "7") (pinfunction "7_7") (pintype "passive"))
      (node (ref "DB6") (pin "7") (pinfunction "7_7") (pintype "passive"))
      (node (ref "DB7") (pin "7") (pinfunction "7_7") (pintype "passive"))
      (node (ref "DB8") (pin "7") (pinfunction "7_7") (pintype "passive"))
      (node (ref "R51") (pin "1") (pinfunction "1_1") (pintype "passive"))
      (node (ref "U$3") (pin "1") (pinfunction "P$1_1") (pintype "bidirectional"))
      (node (ref "U$3") (pin "2") (pinfunction "P$1_2") (pintype "bidirectional"))
      (node (ref "U2") (pin "6") (pinfunction "SDAB_6") (pintype "bidirectional"))
    )
    (net (code "150") (name "U0RX") (class "Default")
      (node (ref "JP6") (pin "1") (pinfunction "1_1") (pintype "passive"))
      (node (ref "JP9") (pin "TXO") (pinfunction "3_TXO") (pintype "passive"))
      (node (ref "U1") (pin "11") (pinfunction "PB00_11") (pintype "bidirectional"))
    )
    (net (code "151") (name "U0TX") (class "Default")
      (node (ref "JP4") (pin "8") (pinfunction "8_8") (pintype "passive"))
      (node (ref "JP9") (pin "RXI") (pinfunction "2_RXI") (pintype "passive"))
      (node (ref "U1") (pin "12") (pinfunction "PB01_12") (pintype "bidirectional"))
    )
    (net (code "152") (name "U1RX") (class "Default")
      (node (ref "JP7") (pin "3") (pinfunction "3_3") (pintype "passive"))
      (node (ref "U1") (pin "57") (pinfunction "PB14_57") (pintype "bidirectional"))
      (node (ref "U4") (pin "6") (pinfunction "OUTB_6") (pintype "bidirectional"))
    )
    (net (code "153") (name "U1TX") (class "Default")
      (node (ref "JP7") (pin "2") (pinfunction "2_2") (pintype "passive"))
      (node (ref "U1") (pin "58") (pinfunction "PB15_58") (pintype "bidirectional"))
      (node (ref "U4") (pin "7") (pinfunction "INA_7") (pintype "bidirectional"))
    )
    (net (code "154") (name "U3RX") (class "Default")
      (node (ref "JP10") (pin "RXI") (pinfunction "2_RXI") (pintype "passive"))
      (node (ref "JP5") (pin "5") (pinfunction "5_5") (pintype "passive"))
      (node (ref "U$1") (pin "14") (pinfunction "UARTTX_14") (pintype "bidirectional"))
      (node (ref "U1") (pin "46") (pinfunction "PB09_46") (pintype "bidirectional"))
    )
    (net (code "155") (name "U3TX") (class "Default")
      (node (ref "JP10") (pin "TXO") (pinfunction "3_TXO") (pintype "passive"))
      (node (ref "JP5") (pin "4") (pinfunction "4_4") (pintype "passive"))
      (node (ref "U$1") (pin "13") (pinfunction "UARTRX_13") (pintype "bidirectional"))
      (node (ref "U1") (pin "47") (pinfunction "PB10_47") (pintype "bidirectional"))
    )
    (net (code "156") (name "VBUSD") (class "Default")
      (node (ref "JP16") (pin "1") (pinfunction "1_1") (pintype "passive"))
      (node (ref "R7") (pin "1") (pinfunction "1_1") (pintype "passive"))
      (node (ref "R8") (pin "2") (pinfunction "2_2") (pintype "passive"))
    )
    (net (code "157") (name "VUSB") (class "Default")
      (node (ref "CN1") (pin "VBUS") (pinfunction "VBUS_VBUS") (pintype "power_in"))
      (node (ref "JP17") (pin "1") (pinfunction "1_1") (pintype "passive"))
      (node (ref "R7") (pin "2") (pinfunction "2_2") (pintype "passive"))
    )
    (net (code "158") (name "unconnected-(CN1-PadID)") (class "Default")
      (node (ref "CN1") (pin "ID") (pinfunction "ID_ID") (pintype "bidirectional"))
    )
    (net (code "159") (name "unconnected-(DB1-Pad9)") (class "Default")
      (node (ref "DB1") (pin "9") (pinfunction "9_9") (pintype "passive"))
    )
    (net (code "160") (name "unconnected-(DB1-Pad11)") (class "Default")
      (node (ref "DB1") (pin "11") (pinfunction "11_11") (pintype "passive"))
    )
    (net (code "161") (name "unconnected-(DB1-Pad15)") (class "Default")
      (node (ref "DB1") (pin "15") (pinfunction "15_15") (pintype "passive"))
    )
    (net (code "162") (name "unconnected-(DB2-Pad9)") (class "Default")
      (node (ref "DB2") (pin "9") (pinfunction "9_9") (pintype "passive"))
    )
    (net (code "163") (name "unconnected-(DB2-Pad11)") (class "Default")
      (node (ref "DB2") (pin "11") (pinfunction "11_11") (pintype "passive"))
    )
    (net (code "164") (name "unconnected-(DB2-Pad15)") (class "Default")
      (node (ref "DB2") (pin "15") (pinfunction "15_15") (pintype "passive"))
    )
    (net (code "165") (name "unconnected-(DB3-Pad9)") (class "Default")
      (node (ref "DB3") (pin "9") (pinfunction "9_9") (pintype "passive"))
    )
    (net (code "166") (name "unconnected-(DB3-Pad11)") (class "Default")
      (node (ref "DB3") (pin "11") (pinfunction "11_11") (pintype "passive"))
    )
    (net (code "167") (name "unconnected-(DB3-Pad15)") (class "Default")
      (node (ref "DB3") (pin "15") (pinfunction "15_15") (pintype "passive"))
    )
    (net (code "168") (name "unconnected-(DB4-Pad9)") (class "Default")
      (node (ref "DB4") (pin "9") (pinfunction "9_9") (pintype "passive"))
    )
    (net (code "169") (name "unconnected-(DB4-Pad11)") (class "Default")
      (node (ref "DB4") (pin "11") (pinfunction "11_11") (pintype "passive"))
    )
    (net (code "170") (name "unconnected-(DB4-Pad15)") (class "Default")
      (node (ref "DB4") (pin "15") (pinfunction "15_15") (pintype "passive"))
    )
    (net (code "171") (name "unconnected-(DB5-Pad9)") (class "Default")
      (node (ref "DB5") (pin "9") (pinfunction "9_9") (pintype "passive"))
    )
    (net (code "172") (name "unconnected-(DB5-Pad11)") (class "Default")
      (node (ref "DB5") (pin "11") (pinfunction "11_11") (pintype "passive"))
    )
    (net (code "173") (name "unconnected-(DB5-Pad15)") (class "Default")
      (node (ref "DB5") (pin "15") (pinfunction "15_15") (pintype "passive"))
    )
    (net (code "174") (name "unconnected-(DB6-Pad9)") (class "Default")
      (node (ref "DB6") (pin "9") (pinfunction "9_9") (pintype "passive"))
    )
    (net (code "175") (name "unconnected-(DB6-Pad11)") (class "Default")
      (node (ref "DB6") (pin "11") (pinfunction "11_11") (pintype "passive"))
    )
    (net (code "176") (name "unconnected-(DB6-Pad15)") (class "Default")
      (node (ref "DB6") (pin "15") (pinfunction "15_15") (pintype "passive"))
    )
    (net (code "177") (name "unconnected-(DB7-Pad9)") (class "Default")
      (node (ref "DB7") (pin "9") (pinfunction "9_9") (pintype "passive"))
    )
    (net (code "178") (name "unconnected-(DB7-Pad11)") (class "Default")
      (node (ref "DB7") (pin "11") (pinfunction "11_11") (pintype "passive"))
    )
    (net (code "179") (name "unconnected-(DB7-Pad15)") (class "Default")
      (node (ref "DB7") (pin "15") (pinfunction "15_15") (pintype "passive"))
    )
    (net (code "180") (name "unconnected-(DB8-Pad9)") (class "Default")
      (node (ref "DB8") (pin "9") (pinfunction "9_9") (pintype "passive"))
    )
    (net (code "181") (name "unconnected-(DB8-Pad11)") (class "Default")
      (node (ref "DB8") (pin "11") (pinfunction "11_11") (pintype "passive"))
    )
    (net (code "182") (name "unconnected-(DB8-Pad15)") (class "Default")
      (node (ref "DB8") (pin "15") (pinfunction "15_15") (pintype "passive"))
    )
    (net (code "183") (name "unconnected-(JP9-1-PadDTR)") (class "Default")
      (node (ref "JP9") (pin "DTR") (pinfunction "1_DTR") (pintype "passive"))
    )
    (net (code "184") (name "unconnected-(JP9-4-PadVCC)") (class "Default")
      (node (ref "JP9") (pin "VCC") (pinfunction "4_VCC") (pintype "passive"))
    )
    (net (code "185") (name "unconnected-(JP9-5-PadCTS)") (class "Default")
      (node (ref "JP9") (pin "CTS") (pinfunction "5_CTS") (pintype "passive"))
    )
    (net (code "186") (name "unconnected-(JP10-1-PadDTR)") (class "Default")
      (node (ref "JP10") (pin "DTR") (pinfunction "1_DTR") (pintype "passive"))
    )
    (net (code "187") (name "unconnected-(JP10-4-PadVCC)") (class "Default")
      (node (ref "JP10") (pin "VCC") (pinfunction "4_VCC") (pintype "passive"))
    )
    (net (code "188") (name "unconnected-(JP10-5-PadCTS)") (class "Default")
      (node (ref "JP10") (pin "CTS") (pinfunction "5_CTS") (pintype "passive"))
    )
    (net (code "189") (name "unconnected-(U$1-AIO0-Pad30)") (class "Default")
      (node (ref "U$1") (pin "30") (pinfunction "AIO0_30") (pintype "bidirectional"))
    )
    (net (code "190") (name "unconnected-(U$1-AIO1-Pad35)") (class "Default")
      (node (ref "U$1") (pin "35") (pinfunction "AIO1_35") (pintype "bidirectional"))
    )
    (net (code "191") (name "unconnected-(U$1-PCMCLK-Pad7)") (class "Default")
      (node (ref "U$1") (pin "7") (pinfunction "PCMCLK_7") (pintype "bidirectional"))
    )
    (net (code "192") (name "unconnected-(U$1-PCMIN-Pad9)") (class "Default")
      (node (ref "U$1") (pin "9") (pinfunction "PCMIN_9") (pintype "bidirectional"))
    )
    (net (code "193") (name "unconnected-(U$1-PCMOUT-Pad10)") (class "Default")
      (node (ref "U$1") (pin "10") (pinfunction "PCMOUT_10") (pintype "bidirectional"))
    )
    (net (code "194") (name "unconnected-(U$1-PCMSYNC-Pad8)") (class "Default")
      (node (ref "U$1") (pin "8") (pinfunction "PCMSYNC_8") (pintype "bidirectional"))
    )
    (net (code "195") (name "unconnected-(U$1-PIO3-Pad20)") (class "Default")
      (node (ref "U$1") (pin "20") (pinfunction "PIO3_20") (pintype "bidirectional"))
    )
    (net (code "196") (name "unconnected-(U$1-PIO6-Pad3)") (class "Default")
      (node (ref "U$1") (pin "3") (pinfunction "PIO6_3") (pintype "bidirectional"))
    )
    (net (code "197") (name "unconnected-(U$1-PIO7-Pad4)") (class "Default")
      (node (ref "U$1") (pin "4") (pinfunction "PIO7_4") (pintype "bidirectional"))
    )
    (net (code "198") (name "unconnected-(U$1-PIO8-Pad31)") (class "Default")
      (node (ref "U$1") (pin "31") (pinfunction "PIO8_31") (pintype "bidirectional"))
    )
    (net (code "199") (name "unconnected-(U$1-PIO9-Pad32)") (class "Default")
      (node (ref "U$1") (pin "32") (pinfunction "PIO9_32") (pintype "bidirectional"))
    )
    (net (code "200") (name "unconnected-(U$1-PIO10-Pad33)") (class "Default")
      (node (ref "U$1") (pin "33") (pinfunction "PIO10_33") (pintype "bidirectional"))
    )
    (net (code "201") (name "unconnected-(U$1-PIO11-Pad34)") (class "Default")
      (node (ref "U$1") (pin "34") (pinfunction "PIO11_34") (pintype "bidirectional"))
    )
    (net (code "202") (name "unconnected-(U$1-RESET-Pad5)") (class "Default")
      (node (ref "U$1") (pin "5") (pinfunction "RESET_5") (pintype "bidirectional"))
    )
    (net (code "203") (name "unconnected-(U$1-SPICLK-Pad6)") (class "Default")
      (node (ref "U$1") (pin "6") (pinfunction "SPICLK_6") (pintype "bidirectional"))
    )
    (net (code "204") (name "unconnected-(U$1-SPICSB-Pad23)") (class "Default")
      (node (ref "U$1") (pin "23") (pinfunction "SPICSB_23") (pintype "bidirectional"))
    )
    (net (code "205") (name "unconnected-(U$1-SPIMISO-Pad24)") (class "Default")
      (node (ref "U$1") (pin "24") (pinfunction "SPIMISO_24") (pintype "bidirectional"))
    )
    (net (code "206") (name "unconnected-(U$1-SPIMOSI-Pad2)") (class "Default")
      (node (ref "U$1") (pin "2") (pinfunction "SPIMOSI_2") (pintype "bidirectional"))
    )
    (net (code "207") (name "unconnected-(U$1-UARTCTS-Pad16)") (class "Default")
      (node (ref "U$1") (pin "16") (pinfunction "UARTCTS_16") (pintype "bidirectional"))
    )
    (net (code "208") (name "unconnected-(U$1-UARTRTS-Pad15)") (class "Default")
      (node (ref "U$1") (pin "15") (pinfunction "UARTRTS_15") (pintype "bidirectional"))
    )
    (net (code "209") (name "unconnected-(U$1-USBD+-Pad17)") (class "Default")
      (node (ref "U$1") (pin "17") (pinfunction "USBD+_17") (pintype "bidirectional"))
    )
    (net (code "210") (name "unconnected-(U$1-USBD--Pad18)") (class "Default")
      (node (ref "U$1") (pin "18") (pinfunction "USBD-_18") (pintype "bidirectional"))
    )
    (net (code "211") (name "unconnected-(U2-EN-Pad5)") (class "Default")
      (node (ref "U2") (pin "5") (pinfunction "EN_5") (pintype "bidirectional"))
    )
    (net (code "212") (name "unconnected-(U3-CTS-Pad11)") (class "Default")
      (node (ref "U3") (pin "11") (pinfunction "CTS_11") (pintype "bidirectional"))
    )
    (net (code "213") (name "unconnected-(U3-DTR-Pad2)") (class "Default")
      (node (ref "U3") (pin "2") (pinfunction "DTR_2") (pintype "bidirectional"))
    )
    (net (code "214") (name "unconnected-(U3-RTS-Pad3)") (class "Default")
      (node (ref "U3") (pin "3") (pinfunction "RTS_3") (pintype "bidirectional"))
    )
  )
)
